# FrequencyCounter.net
KiCad netlist of a schematic drawn in EAGLE
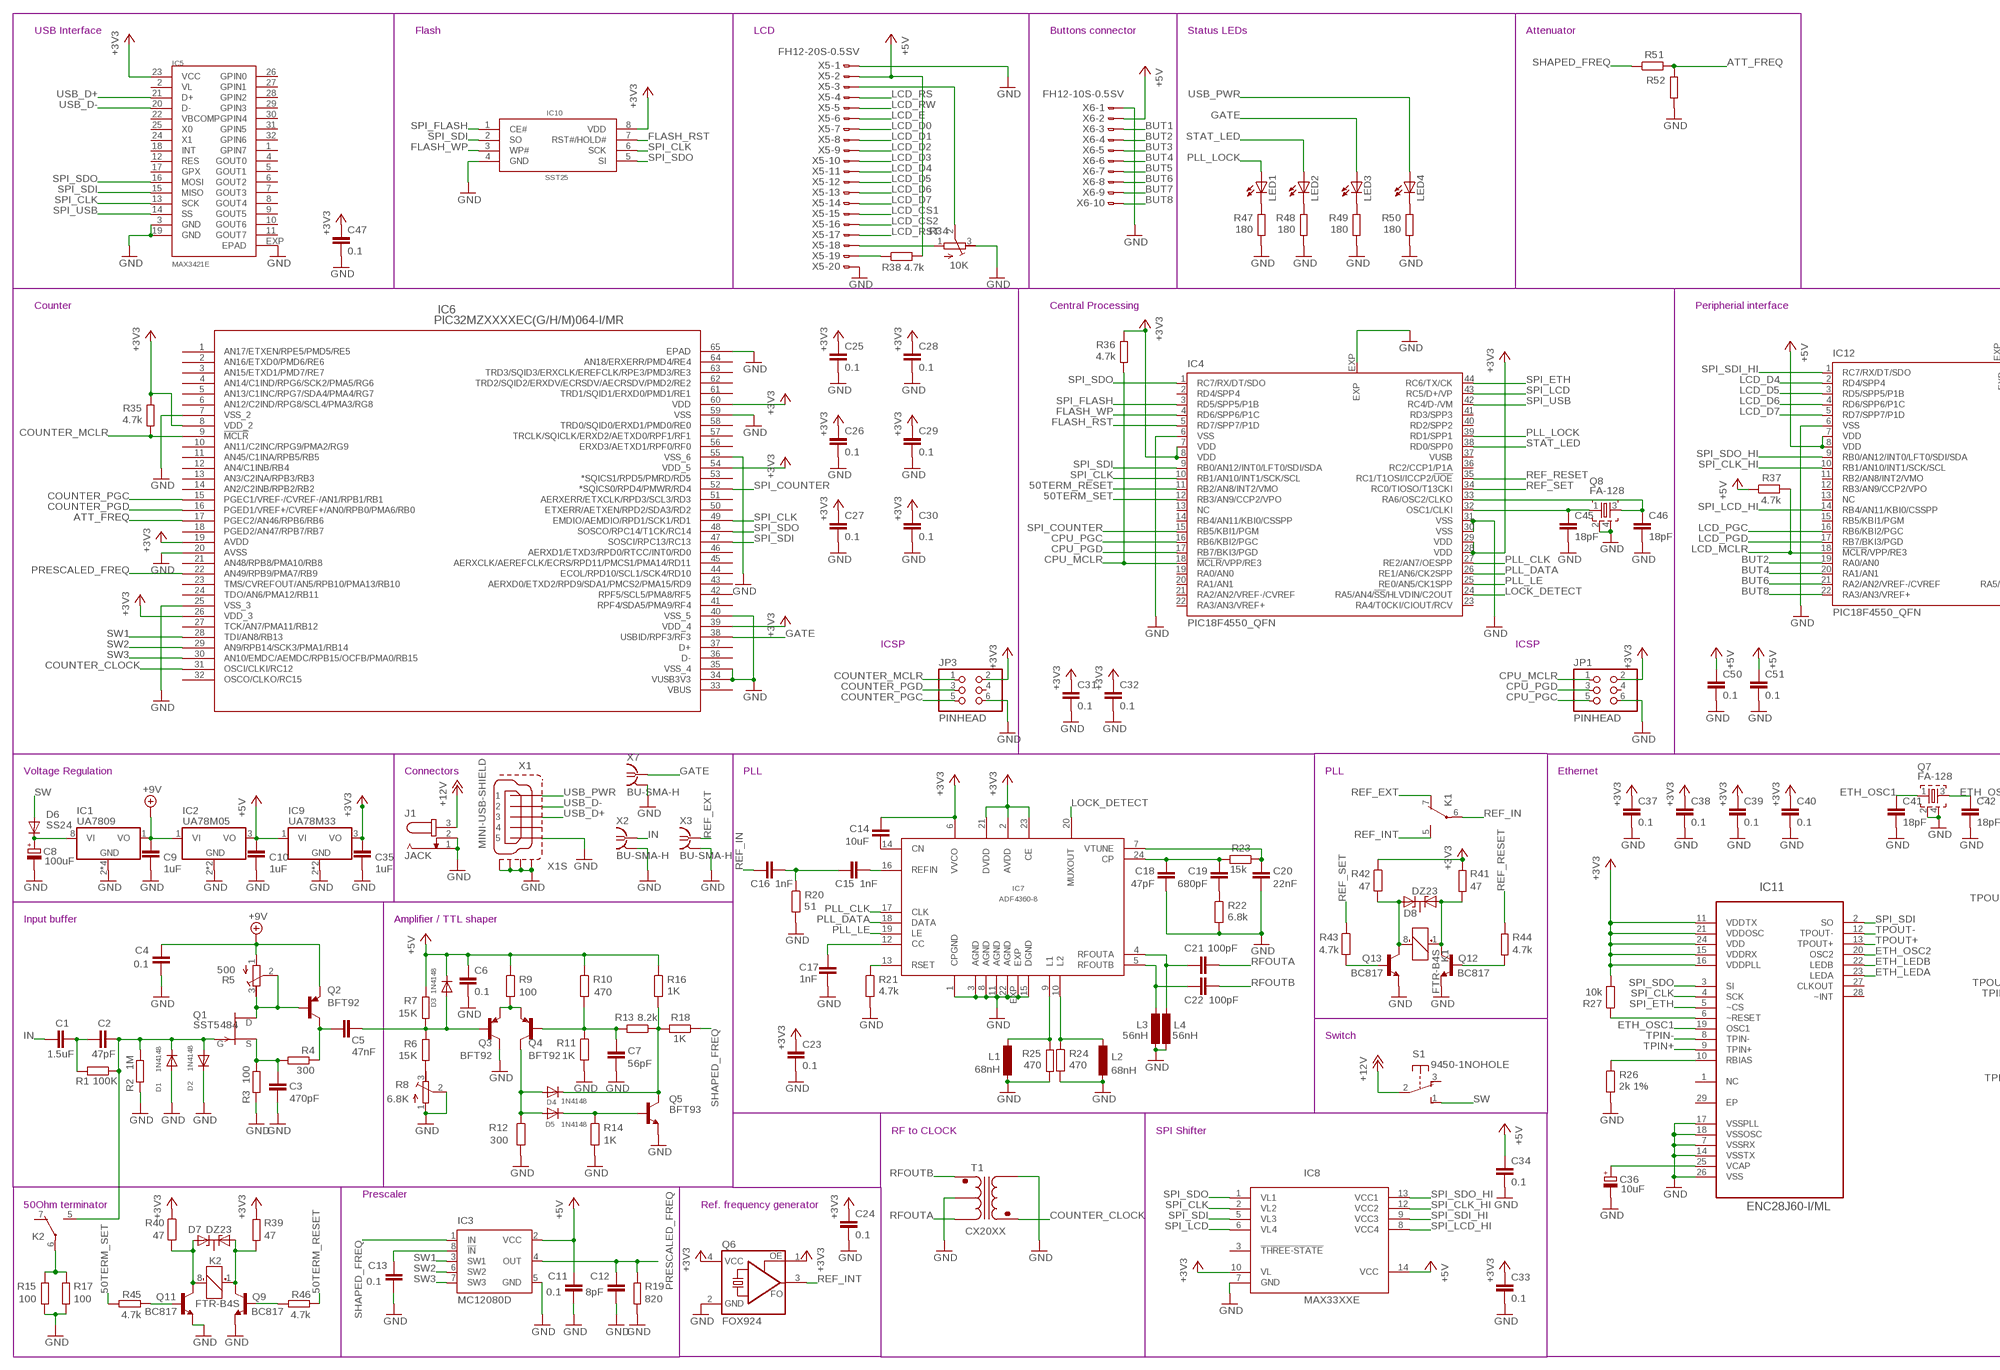
[diagram p0: schematic, sheet 1, part 1 of 2]
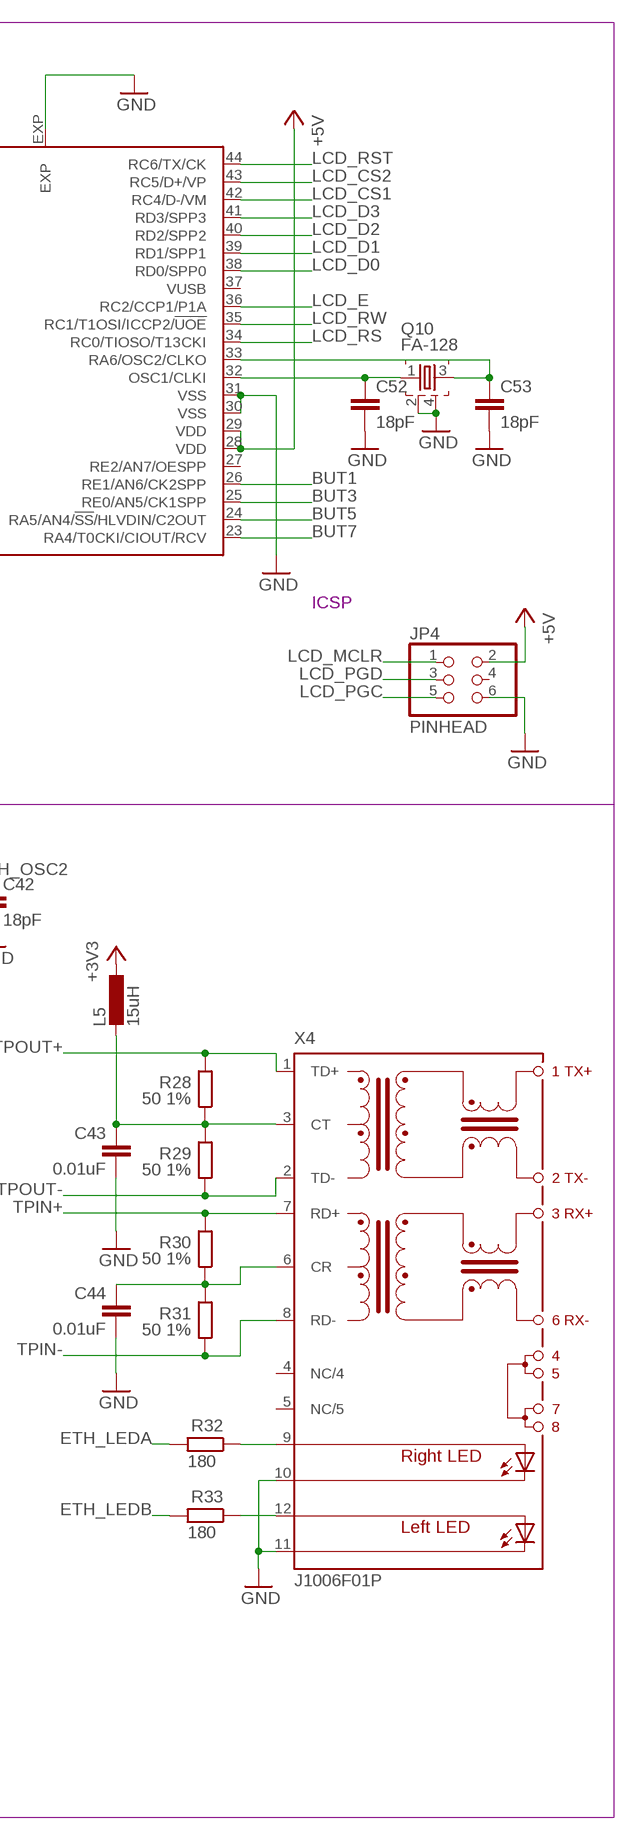
[diagram p1: schematic, sheet 1, part 2 of 2]

(export (version "E")
  (design (tool "Eeschema 10.0.6"))
  (components
    (comp (ref "C1")
      (value "1.5uF")
      (footprint "eagle-import:C0603")
      (libsource (lib "eagle-import") (part "C-EUC0603"))
    )
    (comp (ref "C2")
      (value "47pF")
      (footprint "eagle-import:C0603")
      (libsource (lib "eagle-import") (part "C-EUC0603"))
    )
    (comp (ref "C3")
      (value "470pF")
      (footprint "eagle-import:C0603")
      (libsource (lib "eagle-import") (part "C-EUC0603"))
    )
    (comp (ref "C4")
      (value "0.1")
      (footprint "eagle-import:C0603")
      (libsource (lib "eagle-import") (part "C-EUC0603"))
    )
    (comp (ref "C5")
      (value "47nF")
      (footprint "eagle-import:C0603")
      (libsource (lib "eagle-import") (part "C-EUC0603"))
    )
    (comp (ref "C6")
      (value "0.1")
      (footprint "eagle-import:C0603")
      (libsource (lib "eagle-import") (part "C-EUC0603"))
    )
    (comp (ref "C7")
      (value "56pF")
      (footprint "eagle-import:C0603")
      (libsource (lib "eagle-import") (part "C-EUC0603"))
    )
    (comp (ref "C8")
      (value "100uF")
      (footprint "eagle-import:D_7343-31R")
      (libsource (lib "eagle-import") (part "CPOL-EUD/7343-31R"))
    )
    (comp (ref "C9")
      (value "1uF")
      (footprint "eagle-import:C0603")
      (libsource (lib "eagle-import") (part "C-EUC0603"))
    )
    (comp (ref "C10")
      (value "1uF")
      (footprint "eagle-import:C0603")
      (libsource (lib "eagle-import") (part "C-EUC0603"))
    )
    (comp (ref "C11")
      (value "0.1")
      (footprint "eagle-import:C0603")
      (libsource (lib "eagle-import") (part "C-EUC0603"))
    )
    (comp (ref "C12")
      (value "8pF")
      (footprint "eagle-import:C0603")
      (libsource (lib "eagle-import") (part "C-EUC0603"))
    )
    (comp (ref "C13")
      (value "0.1")
      (footprint "eagle-import:C0603")
      (libsource (lib "eagle-import") (part "C-EUC0603"))
    )
    (comp (ref "C14")
      (value "10uF")
      (footprint "eagle-import:C0603")
      (libsource (lib "eagle-import") (part "C-EUC0603"))
    )
    (comp (ref "C15")
      (value "1nF")
      (footprint "eagle-import:C0603")
      (libsource (lib "eagle-import") (part "C-EUC0603"))
    )
    (comp (ref "C16")
      (value "1nF")
      (footprint "eagle-import:C0603")
      (libsource (lib "eagle-import") (part "C-EUC0603"))
    )
    (comp (ref "C17")
      (value "1nF")
      (footprint "eagle-import:C0603")
      (libsource (lib "eagle-import") (part "C-EUC0603"))
    )
    (comp (ref "C18")
      (value "47pF")
      (footprint "eagle-import:C0603")
      (libsource (lib "eagle-import") (part "C-EUC0603"))
    )
    (comp (ref "C19")
      (value "680pF")
      (footprint "eagle-import:C0603")
      (libsource (lib "eagle-import") (part "C-EUC0603"))
    )
    (comp (ref "C20")
      (value "22nF")
      (footprint "eagle-import:C0603")
      (libsource (lib "eagle-import") (part "C-EUC0603"))
    )
    (comp (ref "C21")
      (value "100pF")
      (footprint "eagle-import:C0603")
      (libsource (lib "eagle-import") (part "C-EUC0603"))
    )
    (comp (ref "C22")
      (value "100pF")
      (footprint "eagle-import:C0603")
      (libsource (lib "eagle-import") (part "C-EUC0603"))
    )
    (comp (ref "C23")
      (value "0.1")
      (footprint "eagle-import:C0603")
      (libsource (lib "eagle-import") (part "C-EUC0603"))
    )
    (comp (ref "C24")
      (value "0.1")
      (footprint "eagle-import:C0603")
      (libsource (lib "eagle-import") (part "C-EUC0603"))
    )
    (comp (ref "C25")
      (value "0.1")
      (footprint "eagle-import:C0603")
      (libsource (lib "eagle-import") (part "C-EUC0603"))
    )
    (comp (ref "C26")
      (value "0.1")
      (footprint "eagle-import:C0603")
      (libsource (lib "eagle-import") (part "C-EUC0603"))
    )
    (comp (ref "C27")
      (value "0.1")
      (footprint "eagle-import:C0603")
      (libsource (lib "eagle-import") (part "C-EUC0603"))
    )
    (comp (ref "C28")
      (value "0.1")
      (footprint "eagle-import:C0603")
      (libsource (lib "eagle-import") (part "C-EUC0603"))
    )
    (comp (ref "C29")
      (value "0.1")
      (footprint "eagle-import:C0603")
      (libsource (lib "eagle-import") (part "C-EUC0603"))
    )
    (comp (ref "C30")
      (value "0.1")
      (footprint "eagle-import:C0603")
      (libsource (lib "eagle-import") (part "C-EUC0603"))
    )
    (comp (ref "C31")
      (value "0.1")
      (footprint "eagle-import:C0603")
      (libsource (lib "eagle-import") (part "C-EUC0603"))
    )
    (comp (ref "C32")
      (value "0.1")
      (footprint "eagle-import:C0603")
      (libsource (lib "eagle-import") (part "C-EUC0603"))
    )
    (comp (ref "C33")
      (value "0.1")
      (footprint "eagle-import:C0603")
      (libsource (lib "eagle-import") (part "C-EUC0603"))
    )
    (comp (ref "C34")
      (value "0.1")
      (footprint "eagle-import:C0603")
      (libsource (lib "eagle-import") (part "C-EUC0603"))
    )
    (comp (ref "C35")
      (value "1uF")
      (footprint "eagle-import:C0603")
      (libsource (lib "eagle-import") (part "C-EUC0603"))
    )
    (comp (ref "C36")
      (value "10uF")
      (footprint "eagle-import:B_3528-21R")
      (libsource (lib "eagle-import") (part "CPOL-EUB/3528-21R"))
    )
    (comp (ref "C37")
      (value "0.1")
      (footprint "eagle-import:C0603")
      (libsource (lib "eagle-import") (part "C-EUC0603"))
    )
    (comp (ref "C38")
      (value "0.1")
      (footprint "eagle-import:C0603")
      (libsource (lib "eagle-import") (part "C-EUC0603"))
    )
    (comp (ref "C39")
      (value "0.1")
      (footprint "eagle-import:C0603")
      (libsource (lib "eagle-import") (part "C-EUC0603"))
    )
    (comp (ref "C40")
      (value "0.1")
      (footprint "eagle-import:C0603")
      (libsource (lib "eagle-import") (part "C-EUC0603"))
    )
    (comp (ref "C41")
      (value "18pF")
      (footprint "eagle-import:C0603")
      (libsource (lib "eagle-import") (part "C-EUC0603"))
    )
    (comp (ref "C42")
      (value "18pF")
      (footprint "eagle-import:C0603")
      (libsource (lib "eagle-import") (part "C-EUC0603"))
    )
    (comp (ref "C43")
      (value "0.01uF")
      (footprint "eagle-import:C0603")
      (libsource (lib "eagle-import") (part "C-EUC0603"))
    )
    (comp (ref "C44")
      (value "0.01uF")
      (footprint "eagle-import:C0603")
      (libsource (lib "eagle-import") (part "C-EUC0603"))
    )
    (comp (ref "C45")
      (value "18pF")
      (footprint "eagle-import:C0603")
      (libsource (lib "eagle-import") (part "C-EUC0603"))
    )
    (comp (ref "C46")
      (value "18pF")
      (footprint "eagle-import:C0603")
      (libsource (lib "eagle-import") (part "C-EUC0603"))
    )
    (comp (ref "C47")
      (value "0.1")
      (footprint "eagle-import:C0603")
      (libsource (lib "eagle-import") (part "C-EUC0603"))
    )
    (comp (ref "C50")
      (value "0.1")
      (footprint "eagle-import:C0603")
      (libsource (lib "eagle-import") (part "C-EUC0603"))
    )
    (comp (ref "C51")
      (value "0.1")
      (footprint "eagle-import:C0603")
      (libsource (lib "eagle-import") (part "C-EUC0603"))
    )
    (comp (ref "C52")
      (value "18pF")
      (footprint "eagle-import:C0603")
      (libsource (lib "eagle-import") (part "C-EUC0603"))
    )
    (comp (ref "C53")
      (value "18pF")
      (footprint "eagle-import:C0603")
      (libsource (lib "eagle-import") (part "C-EUC0603"))
    )
    (comp (ref "D1")
      (value "1N4148")
      (footprint "eagle-import:SOD-123")
      (libsource (lib "eagle-import") (part "DIODESOD-123"))
    )
    (comp (ref "D2")
      (value "1N4148")
      (footprint "eagle-import:SOD-123")
      (libsource (lib "eagle-import") (part "DIODESOD-123"))
    )
    (comp (ref "D3")
      (value "1N4148")
      (footprint "eagle-import:SOD-123")
      (libsource (lib "eagle-import") (part "DIODESOD-123"))
    )
    (comp (ref "D4")
      (value "1N4148")
      (footprint "eagle-import:SOD-123")
      (libsource (lib "eagle-import") (part "DIODESOD-123"))
    )
    (comp (ref "D5")
      (value "1N4148")
      (footprint "eagle-import:SOD-123")
      (libsource (lib "eagle-import") (part "DIODESOD-123"))
    )
    (comp (ref "D6")
      (value "SS24")
      (footprint "eagle-import:DO214AA")
      (libsource (lib "eagle-import") (part "DIODE-DO214AA"))
    )
    (comp (ref "D7")
      (value "DZ23")
      (footprint "eagle-import:SOT23")
      (libsource (lib "eagle-import") (part "DZ23"))
    )
    (comp (ref "D8")
      (value "DZ23")
      (footprint "eagle-import:SOT23")
      (libsource (lib "eagle-import") (part "DZ23"))
    )
    (comp (ref "IC1")
      (value "UA7809")
      (footprint "eagle-import:SOIC8")
      (libsource (lib "eagle-import") (part "UA78XX"))
    )
    (comp (ref "IC2")
      (value "UA78M05")
      (footprint "eagle-import:SOT223")
      (libsource (lib "eagle-import") (part "UA78MXX"))
    )
    (comp (ref "IC3")
      (value "MC12080D")
      (footprint "eagle-import:SO08")
      (fields (field (name "MF") "ON SEMICONDUCTOR"))
      (libsource (lib "eagle-import") (part "MC12080D"))
    )
    (comp (ref "IC4")
      (value "PIC18F4550_QFN")
      (footprint "eagle-import:QFN44ML8X8")
      (fields (field (name "MF") "MICROCHIP") (field (name "MPN") "PIC18F4550-I/ML"))
      (libsource (lib "eagle-import") (part "PIC18F4_QFN550"))
    )
    (comp (ref "IC5")
      (value "MAX3421E")
      (footprint "eagle-import:TQFN32")
      (libsource (lib "eagle-import") (part "MAX3421ETQFN32"))
    )
    (comp (ref "IC6")
      (value "PIC32MZXXXXEC(G/H/M)064-I/MR")
      (footprint "eagle-import:QFN64_9X9MC")
      (fields (field (name "MANUFACTURER_PART_NUMBER") "pic32mz1024ecg064-i/mr"))
      (libsource (lib "eagle-import") (part "PIC32MZXXXXEC(G/H/M)064-I/MR"))
    )
    (comp (ref "IC7")
      (value "ADF4360-8")
      (footprint "eagle-import:LFCSP24")
      (libsource (lib "eagle-import") (part "ADF4360"))
    )
    (comp (ref "IC8")
      (value "MAX33XXE")
      (footprint "eagle-import:TSSOP14")
      (libsource (lib "eagle-import") (part "MAX33XXE"))
    )
    (comp (ref "IC9")
      (value "UA78M33")
      (footprint "eagle-import:SOT223")
      (libsource (lib "eagle-import") (part "UA78MXX"))
    )
    (comp (ref "IC10")
      (value "SST25")
      (footprint "eagle-import:SOIC8")
      (libsource (lib "eagle-import") (part "SST25"))
    )
    (comp (ref "IC11")
      (value "ENC28J60-I/ML")
      (footprint "eagle-import:QFN65P600X600X100-29N")
      (libsource (lib "eagle-import") (part "ENC28J60-I/ML"))
    )
    (comp (ref "IC12")
      (value "PIC18F4550_QFN")
      (footprint "eagle-import:QFN44ML8X8")
      (fields (field (name "MF") "MICROCHIP") (field (name "MPN") "PIC18F4550-I/ML"))
      (libsource (lib "eagle-import") (part "PIC18F4_QFN550"))
    )
    (comp (ref "J1")
      (value "JACK")
      (footprint "eagle-import:SPC4077")
      (libsource (lib "eagle-import") (part "JACK-PLUG0"))
    )
    (comp (ref "JP1")
      (value "PINHEAD")
      (footprint "eagle-import:2X03_1.27")
      (libsource (lib "eagle-import") (part "PINHD-2X32X03/1.27MM"))
    )
    (comp (ref "JP3")
      (value "PINHEAD")
      (footprint "eagle-import:2X03_1.27")
      (libsource (lib "eagle-import") (part "PINHD-2X32X03/1.27MM"))
    )
    (comp (ref "JP4")
      (value "PINHEAD")
      (footprint "eagle-import:2X03_1.27")
      (libsource (lib "eagle-import") (part "PINHD-2X32X03/1.27MM"))
    )
    (comp (ref "K1")
      (value "FTR-B4S")
      (footprint "eagle-import:FTR-B4S")
      (libsource (lib "eagle-import") (part "FTR-B4S"))
    )
    (comp (ref "K2")
      (value "FTR-B4S")
      (footprint "eagle-import:FTR-B4S")
      (libsource (lib "eagle-import") (part "FTR-B4S"))
    )
    (comp (ref "L1")
      (value "68nH")
      (footprint "eagle-import:L2012C")
      (libsource (lib "eagle-import") (part "L-EUL2012C"))
    )
    (comp (ref "L2")
      (value "68nH")
      (footprint "eagle-import:L2012C")
      (libsource (lib "eagle-import") (part "L-EUL2012C"))
    )
    (comp (ref "L3")
      (value "56nH")
      (footprint "eagle-import:L2012C")
      (libsource (lib "eagle-import") (part "L-EUL2012C"))
    )
    (comp (ref "L4")
      (value "56nH")
      (footprint "eagle-import:L2012C")
      (libsource (lib "eagle-import") (part "L-EUL2012C"))
    )
    (comp (ref "L5")
      (value "15uH")
      (footprint "eagle-import:L2012C")
      (libsource (lib "eagle-import") (part "resistor_L-EUL2012C"))
    )
    (comp (ref "LED1")
      (value "LEDCHIP-LED0805")
      (footprint "eagle-import:CHIP-LED0805")
      (libsource (lib "eagle-import") (part "LEDCHIP-LED0805"))
    )
    (comp (ref "LED2")
      (value "LEDCHIP-LED0805")
      (footprint "eagle-import:CHIP-LED0805")
      (libsource (lib "eagle-import") (part "LEDCHIP-LED0805"))
    )
    (comp (ref "LED3")
      (value "LEDCHIP-LED0805")
      (footprint "eagle-import:CHIP-LED0805")
      (libsource (lib "eagle-import") (part "LEDCHIP-LED0805"))
    )
    (comp (ref "LED4")
      (value "LEDCHIP-LED0805")
      (footprint "eagle-import:CHIP-LED0805")
      (libsource (lib "eagle-import") (part "LEDCHIP-LED0805"))
    )
    (comp (ref "Q1")
      (value "SST5484")
      (footprint "eagle-import:SOT23")
      (libsource (lib "eagle-import") (part "?548SST4"))
    )
    (comp (ref "Q2")
      (value "BFT92")
      (footprint "eagle-import:SOT23-BEC")
      (libsource (lib "eagle-import") (part "-PNP-SOT23-BECBC807-16"))
    )
    (comp (ref "Q3")
      (value "BFT92")
      (footprint "eagle-import:SOT23-BEC")
      (libsource (lib "eagle-import") (part "-PNP-SOT23-BECBC807-16"))
    )
    (comp (ref "Q4")
      (value "BFT92")
      (footprint "eagle-import:SOT23-BEC")
      (libsource (lib "eagle-import") (part "-PNP-SOT23-BECBC807-16"))
    )
    (comp (ref "Q5")
      (value "BFT93")
      (footprint "eagle-import:SOT23-BEC")
      (libsource (lib "eagle-import") (part "-NPN-SOT23-BECBC808"))
    )
    (comp (ref "Q6")
      (value "FOX924")
      (footprint "eagle-import:FOX924")
      (libsource (lib "eagle-import") (part "FOX924"))
    )
    (comp (ref "Q7")
      (value "FA-128")
      (footprint "eagle-import:FA-128")
      (libsource (lib "eagle-import") (part "FA-128"))
    )
    (comp (ref "Q8")
      (value "FA-128")
      (footprint "eagle-import:FA-128")
      (libsource (lib "eagle-import") (part "FA-128"))
    )
    (comp (ref "Q9")
      (value "BC817")
      (footprint "eagle-import:SOT23-BEC")
      (libsource (lib "eagle-import") (part "-NPN-SOT23-BECBC817-16"))
    )
    (comp (ref "Q10")
      (value "FA-128")
      (footprint "eagle-import:FA-128")
      (libsource (lib "eagle-import") (part "FA-128"))
    )
    (comp (ref "Q11")
      (value "BC817")
      (footprint "eagle-import:SOT23-BEC")
      (libsource (lib "eagle-import") (part "-NPN-SOT23-BECBC817-16"))
    )
    (comp (ref "Q12")
      (value "BC817")
      (footprint "eagle-import:SOT23-BEC")
      (libsource (lib "eagle-import") (part "-NPN-SOT23-BECBC817-16"))
    )
    (comp (ref "Q13")
      (value "BC817")
      (footprint "eagle-import:SOT23-BEC")
      (libsource (lib "eagle-import") (part "-NPN-SOT23-BECBC817-16"))
    )
    (comp (ref "R1")
      (value "100K")
      (footprint "eagle-import:R0603")
      (libsource (lib "eagle-import") (part "R-EU_R0603"))
    )
    (comp (ref "R2")
      (value "1M")
      (footprint "eagle-import:R0603")
      (libsource (lib "eagle-import") (part "R-EU_R0603"))
    )
    (comp (ref "R3")
      (value "100")
      (footprint "eagle-import:R0603")
      (libsource (lib "eagle-import") (part "R-EU_R0603"))
    )
    (comp (ref "R4")
      (value "300")
      (footprint "eagle-import:R0603")
      (libsource (lib "eagle-import") (part "R-EU_R0603"))
    )
    (comp (ref "R5")
      (value "500")
      (footprint "eagle-import:RTRIM4G_J")
      (libsource (lib "eagle-import") (part "R-TRIMM4G/J"))
    )
    (comp (ref "R6")
      (value "15K")
      (footprint "eagle-import:R0603")
      (libsource (lib "eagle-import") (part "R-EU_R0603"))
    )
    (comp (ref "R7")
      (value "15K")
      (footprint "eagle-import:R0603")
      (libsource (lib "eagle-import") (part "R-EU_R0603"))
    )
    (comp (ref "R8")
      (value "6.8K")
      (footprint "eagle-import:RTRIM4G_J")
      (libsource (lib "eagle-import") (part "R-TRIMM4G/J"))
    )
    (comp (ref "R9")
      (value "100")
      (footprint "eagle-import:R0603")
      (libsource (lib "eagle-import") (part "R-EU_R0603"))
    )
    (comp (ref "R10")
      (value "470")
      (footprint "eagle-import:R0603")
      (libsource (lib "eagle-import") (part "R-EU_R0603"))
    )
    (comp (ref "R11")
      (value "1K")
      (footprint "eagle-import:R0603")
      (libsource (lib "eagle-import") (part "R-EU_R0603"))
    )
    (comp (ref "R12")
      (value "300")
      (footprint "eagle-import:R0603")
      (libsource (lib "eagle-import") (part "R-EU_R0603"))
    )
    (comp (ref "R13")
      (value "8.2k")
      (footprint "eagle-import:R0603")
      (libsource (lib "eagle-import") (part "R-EU_R0603"))
    )
    (comp (ref "R14")
      (value "1K")
      (footprint "eagle-import:R0603")
      (libsource (lib "eagle-import") (part "R-EU_R0603"))
    )
    (comp (ref "R15")
      (value "100")
      (footprint "eagle-import:R0603")
      (libsource (lib "eagle-import") (part "R-EU_R0603"))
    )
    (comp (ref "R16")
      (value "1K")
      (footprint "eagle-import:R0603")
      (libsource (lib "eagle-import") (part "R-EU_R0603"))
    )
    (comp (ref "R17")
      (value "100")
      (footprint "eagle-import:R0603")
      (libsource (lib "eagle-import") (part "R-EU_R0603"))
    )
    (comp (ref "R18")
      (value "1K")
      (footprint "eagle-import:R0603")
      (libsource (lib "eagle-import") (part "R-EU_R0603"))
    )
    (comp (ref "R19")
      (value "820")
      (footprint "eagle-import:R0603")
      (libsource (lib "eagle-import") (part "R-EU_R0603"))
    )
    (comp (ref "R20")
      (value "51")
      (footprint "eagle-import:R0603")
      (libsource (lib "eagle-import") (part "R-EU_R0603"))
    )
    (comp (ref "R21")
      (value "4.7k")
      (footprint "eagle-import:R0603")
      (libsource (lib "eagle-import") (part "R-EU_R0603"))
    )
    (comp (ref "R22")
      (value "6.8k")
      (footprint "eagle-import:R0603")
      (libsource (lib "eagle-import") (part "R-EU_R0603"))
    )
    (comp (ref "R23")
      (value "15k")
      (footprint "eagle-import:R0603")
      (libsource (lib "eagle-import") (part "R-EU_R0603"))
    )
    (comp (ref "R24")
      (value "470")
      (footprint "eagle-import:R0603")
      (libsource (lib "eagle-import") (part "R-EU_R0603"))
    )
    (comp (ref "R25")
      (value "470")
      (footprint "eagle-import:R0603")
      (libsource (lib "eagle-import") (part "R-EU_R0603"))
    )
    (comp (ref "R26")
      (value "2k 1%")
      (footprint "eagle-import:R0603")
      (libsource (lib "eagle-import") (part "R-EU_R0603"))
    )
    (comp (ref "R27")
      (value "10k")
      (footprint "eagle-import:R0603")
      (libsource (lib "eagle-import") (part "R-EU_R0603"))
    )
    (comp (ref "R28")
      (value "50 1%")
      (footprint "eagle-import:R0603")
      (libsource (lib "eagle-import") (part "R-EU_R0603"))
    )
    (comp (ref "R29")
      (value "50 1%")
      (footprint "eagle-import:R0603")
      (libsource (lib "eagle-import") (part "R-EU_R0603"))
    )
    (comp (ref "R30")
      (value "50 1%")
      (footprint "eagle-import:R0603")
      (libsource (lib "eagle-import") (part "R-EU_R0603"))
    )
    (comp (ref "R31")
      (value "50 1%")
      (footprint "eagle-import:R0603")
      (libsource (lib "eagle-import") (part "R-EU_R0603"))
    )
    (comp (ref "R32")
      (value "180")
      (footprint "eagle-import:R0603")
      (libsource (lib "eagle-import") (part "R-EU_R0603"))
    )
    (comp (ref "R33")
      (value "180")
      (footprint "eagle-import:R0603")
      (libsource (lib "eagle-import") (part "R-EU_R0603"))
    )
    (comp (ref "R34")
      (value "10K")
      (footprint "eagle-import:RTRIM4G_J")
      (libsource (lib "eagle-import") (part "R-TRIMM4G/J"))
    )
    (comp (ref "R35")
      (value "4.7k")
      (footprint "eagle-import:R0603")
      (libsource (lib "eagle-import") (part "R-EU_R0603"))
    )
    (comp (ref "R36")
      (value "4.7k")
      (footprint "eagle-import:R0603")
      (libsource (lib "eagle-import") (part "R-EU_R0603"))
    )
    (comp (ref "R37")
      (value "4.7k")
      (footprint "eagle-import:R0603")
      (libsource (lib "eagle-import") (part "R-EU_R0603"))
    )
    (comp (ref "R38")
      (value "4.7k")
      (footprint "eagle-import:R0603")
      (libsource (lib "eagle-import") (part "R-EU_R0603"))
    )
    (comp (ref "R39")
      (value "47")
      (footprint "eagle-import:R0603")
      (libsource (lib "eagle-import") (part "R-EU_R0603"))
    )
    (comp (ref "R40")
      (value "47")
      (footprint "eagle-import:R0603")
      (libsource (lib "eagle-import") (part "R-EU_R0603"))
    )
    (comp (ref "R41")
      (value "47")
      (footprint "eagle-import:R0603")
      (libsource (lib "eagle-import") (part "R-EU_R0603"))
    )
    (comp (ref "R42")
      (value "47")
      (footprint "eagle-import:R0603")
      (libsource (lib "eagle-import") (part "R-EU_R0603"))
    )
    (comp (ref "R43")
      (value "4.7k")
      (footprint "eagle-import:R0603")
      (libsource (lib "eagle-import") (part "R-EU_R0603"))
    )
    (comp (ref "R44")
      (value "4.7k")
      (footprint "eagle-import:R0603")
      (libsource (lib "eagle-import") (part "R-EU_R0603"))
    )
    (comp (ref "R45")
      (value "4.7k")
      (footprint "eagle-import:R0603")
      (libsource (lib "eagle-import") (part "R-EU_R0603"))
    )
    (comp (ref "R46")
      (value "4.7k")
      (footprint "eagle-import:R0603")
      (libsource (lib "eagle-import") (part "R-EU_R0603"))
    )
    (comp (ref "R47")
      (value "180")
      (footprint "eagle-import:R0603")
      (libsource (lib "eagle-import") (part "R-EU_R0603"))
    )
    (comp (ref "R48")
      (value "180")
      (footprint "eagle-import:R0603")
      (libsource (lib "eagle-import") (part "R-EU_R0603"))
    )
    (comp (ref "R49")
      (value "180")
      (footprint "eagle-import:R0603")
      (libsource (lib "eagle-import") (part "R-EU_R0603"))
    )
    (comp (ref "R50")
      (value "180")
      (footprint "eagle-import:R0603")
      (libsource (lib "eagle-import") (part "R-EU_R0603"))
    )
    (comp (ref "R51")
      (value "R-EU_R0603")
      (footprint "eagle-import:R0603")
      (libsource (lib "eagle-import") (part "R-EU_R0603"))
    )
    (comp (ref "R52")
      (value "R-EU_R0603")
      (footprint "eagle-import:R0603")
      (libsource (lib "eagle-import") (part "R-EU_R0603"))
    )
    (comp (ref "S1")
      (value "9450-1NOHOLE")
      (footprint "eagle-import:9450-1-NOHOLE")
      (libsource (lib "eagle-import") (part "9450-1NOHOLE"))
    )
    (comp (ref "T1")
      (value "CX20XX")
      (footprint "eagle-import:PULSE_CX20")
      (libsource (lib "eagle-import") (part "CX20XX"))
    )
    (comp (ref "X1")
      (value "MINI-USB-SHIELD")
      (footprint "eagle-import:UX60A-MB-5ST")
      (libsource (lib "eagle-import") (part "MINI-USB-SHIELD-UX60A-MB-5ST"))
    )
    (comp (ref "X2")
      (value "BU-SMA-H")
      (footprint "eagle-import:BU-SMA-H")
      (libsource (lib "eagle-import") (part "BU-SMA-H"))
    )
    (comp (ref "X3")
      (value "BU-SMA-H")
      (footprint "eagle-import:BU-SMA-H")
      (libsource (lib "eagle-import") (part "BU-SMA-H"))
    )
    (comp (ref "X4")
      (value "J1006F01P")
      (footprint "eagle-import:J1")
      (libsource (lib "eagle-import") (part "J1006F01P"))
    )
    (comp (ref "X5")
      (value "FH12-20S-0.5SV")
      (footprint "eagle-import:FH12-20S-0.5SV")
      (libsource (lib "eagle-import") (part "FH12-20S-0.5SV"))
    )
    (comp (ref "X6")
      (value "FH12-10S-0.5SV")
      (footprint "eagle-import:FH12-10S-0.5SV")
      (libsource (lib "eagle-import") (part "FH12-10S-0.5SV"))
    )
    (comp (ref "X7")
      (value "BU-SMA-H")
      (footprint "eagle-import:BU-SMA-H")
      (libsource (lib "eagle-import") (part "BU-SMA-H"))
    )
  )
  (nets
    (net (code "1") (name "+3V3") (class "Default")
      (node (ref "C14") (pin "2") (pinfunction "2_2") (pintype "passive"))
      (node (ref "C23") (pin "1") (pinfunction "1_1") (pintype "passive"))
      (node (ref "C24") (pin "1") (pinfunction "1_1") (pintype "passive"))
      (node (ref "C25") (pin "1") (pinfunction "1_1") (pintype "passive"))
      (node (ref "C26") (pin "1") (pinfunction "1_1") (pintype "passive"))
      (node (ref "C27") (pin "1") (pinfunction "1_1") (pintype "passive"))
      (node (ref "C28") (pin "1") (pinfunction "1_1") (pintype "passive"))
      (node (ref "C29") (pin "1") (pinfunction "1_1") (pintype "passive"))
      (node (ref "C30") (pin "1") (pinfunction "1_1") (pintype "passive"))
      (node (ref "C31") (pin "1") (pinfunction "1_1") (pintype "passive"))
      (node (ref "C32") (pin "1") (pinfunction "1_1") (pintype "passive"))
      (node (ref "C33") (pin "1") (pinfunction "1_1") (pintype "passive"))
      (node (ref "C35") (pin "1") (pinfunction "1_1") (pintype "passive"))
      (node (ref "C37") (pin "1") (pinfunction "1_1") (pintype "passive"))
      (node (ref "C38") (pin "1") (pinfunction "1_1") (pintype "passive"))
      (node (ref "C39") (pin "1") (pinfunction "1_1") (pintype "passive"))
      (node (ref "C40") (pin "1") (pinfunction "1_1") (pintype "passive"))
      (node (ref "C47") (pin "1") (pinfunction "1_1") (pintype "passive"))
      (node (ref "IC10") (pin "8") (pinfunction "VDD_8") (pintype "power_in"))
      (node (ref "IC11") (pin "11") (pinfunction "VDDTX_11") (pintype "power_in"))
      (node (ref "IC11") (pin "15") (pinfunction "VDDRX_15") (pintype "power_in"))
      (node (ref "IC11") (pin "16") (pinfunction "VDDPLL_16") (pintype "power_in"))
      (node (ref "IC11") (pin "21") (pinfunction "VDDOSC_21") (pintype "power_in"))
      (node (ref "IC11") (pin "24") (pinfunction "VDD_24") (pintype "power_in"))
      (node (ref "IC4") (pin "28") (pinfunction "VDD_28") (pintype "power_in"))
      (node (ref "IC4") (pin "29") (pinfunction "VDD_29") (pintype "power_in"))
      (node (ref "IC4") (pin "7") (pinfunction "VDD_7") (pintype "power_in"))
      (node (ref "IC4") (pin "8") (pinfunction "VDD_8") (pintype "power_in"))
      (node (ref "IC5") (pin "23") (pinfunction "VCC_23") (pintype "bidirectional"))
      (node (ref "IC6") (pin "19") (pinfunction "AVDD_19") (pintype "power_in"))
      (node (ref "IC6") (pin "26") (pinfunction "VDD_3_26") (pintype "power_in"))
      (node (ref "IC6") (pin "39") (pinfunction "VDD_4_39") (pintype "power_in"))
      (node (ref "IC6") (pin "54") (pinfunction "VDD_5_54") (pintype "power_in"))
      (node (ref "IC6") (pin "60") (pinfunction "VDD_60") (pintype "power_in"))
      (node (ref "IC6") (pin "8") (pinfunction "VDD_2_8") (pintype "power_in"))
      (node (ref "IC7") (pin "2") (pinfunction "AVDD_2") (pintype "bidirectional"))
      (node (ref "IC7") (pin "21") (pinfunction "DVDD_21") (pintype "bidirectional"))
      (node (ref "IC7") (pin "23") (pinfunction "CE_23") (pintype "bidirectional"))
      (node (ref "IC7") (pin "6") (pinfunction "VVCO_6") (pintype "bidirectional"))
      (node (ref "IC8") (pin "10") (pinfunction "VL_10") (pintype "power_in"))
      (node (ref "IC9") (pin "3") (pinfunction "VO_3") (pintype "passive"))
      (node (ref "JP1") (pin "2") (pinfunction "2_2") (pintype "passive"))
      (node (ref "JP3") (pin "2") (pinfunction "2_2") (pintype "passive"))
      (node (ref "L5") (pin "1") (pinfunction "1_1") (pintype "passive"))
      (node (ref "Q6") (pin "1") (pinfunction "OE_1") (pintype "input"))
      (node (ref "Q6") (pin "4") (pinfunction "VCC_4") (pintype "power_in"))
      (node (ref "R27") (pin "2") (pinfunction "2_2") (pintype "passive"))
      (node (ref "R35") (pin "1") (pinfunction "1_1") (pintype "passive"))
      (node (ref "R36") (pin "1") (pinfunction "1_1") (pintype "passive"))
      (node (ref "R39") (pin "1") (pinfunction "1_1") (pintype "passive"))
      (node (ref "R40") (pin "1") (pinfunction "1_1") (pintype "passive"))
      (node (ref "R41") (pin "1") (pinfunction "1_1") (pintype "passive"))
      (node (ref "R42") (pin "1") (pinfunction "1_1") (pintype "passive"))
    )
    (net (code "2") (name "+5V") (class "Default")
      (node (ref "C10") (pin "1") (pinfunction "1_1") (pintype "passive"))
      (node (ref "C11") (pin "1") (pinfunction "1_1") (pintype "passive"))
      (node (ref "C34") (pin "1") (pinfunction "1_1") (pintype "passive"))
      (node (ref "C50") (pin "1") (pinfunction "1_1") (pintype "passive"))
      (node (ref "C51") (pin "1") (pinfunction "1_1") (pintype "passive"))
      (node (ref "C6") (pin "1") (pinfunction "1_1") (pintype "passive"))
      (node (ref "D3") (pin "C") (pinfunction "C_C") (pintype "passive"))
      (node (ref "IC12") (pin "28") (pinfunction "VDD_28") (pintype "power_in"))
      (node (ref "IC12") (pin "29") (pinfunction "VDD_29") (pintype "power_in"))
      (node (ref "IC12") (pin "7") (pinfunction "VDD_7") (pintype "power_in"))
      (node (ref "IC12") (pin "8") (pinfunction "VDD_8") (pintype "power_in"))
      (node (ref "IC2") (pin "3") (pinfunction "VO_3") (pintype "passive"))
      (node (ref "IC3") (pin "2") (pinfunction "VCC_2") (pintype "power_in"))
      (node (ref "IC8") (pin "14") (pinfunction "VCC_14") (pintype "power_in"))
      (node (ref "IC9") (pin "1") (pinfunction "VI_1") (pintype "input"))
      (node (ref "JP4") (pin "2") (pinfunction "2_2") (pintype "passive"))
      (node (ref "R10") (pin "1") (pinfunction "1_1") (pintype "passive"))
      (node (ref "R16") (pin "1") (pinfunction "1_1") (pintype "passive"))
      (node (ref "R37") (pin "1") (pinfunction "1_1") (pintype "passive"))
      (node (ref "R38") (pin "2") (pinfunction "2_2") (pintype "passive"))
      (node (ref "R7") (pin "1") (pinfunction "1_1") (pintype "passive"))
      (node (ref "R9") (pin "1") (pinfunction "1_1") (pintype "passive"))
      (node (ref "X5") (pin "2") (pinfunction "1_2") (pintype "passive"))
      (node (ref "X6") (pin "2") (pinfunction "1_2") (pintype "passive"))
    )
    (net (code "3") (name "+9V") (class "Default")
      (node (ref "C4") (pin "1") (pinfunction "1_1") (pintype "passive"))
      (node (ref "C9") (pin "1") (pinfunction "1_1") (pintype "passive"))
      (node (ref "IC1") (pin "1") (pinfunction "VO_1") (pintype "passive"))
      (node (ref "IC2") (pin "1") (pinfunction "VI_1") (pintype "input"))
      (node (ref "Q2") (pin "E") (pinfunction "E_E") (pintype "passive"))
      (node (ref "R5") (pin "1") (pinfunction "A_1") (pintype "passive"))
    )
    (net (code "4") (name "+12V") (class "Default")
      (node (ref "J1") (pin "3") (pinfunction "3_3") (pintype "passive"))
      (node (ref "S1") (pin "2") (pinfunction "P_2") (pintype "passive"))
    )
    (net (code "5") (name "/50TERM_RESET") (class "Default")
      (node (ref "IC4") (pin "11") (pinfunction "RB2/AN8/INT2/VMO_11") (pintype "bidirectional"))
      (node (ref "R46") (pin "2") (pinfunction "2_2") (pintype "passive"))
    )
    (net (code "6") (name "/50TERM_SET") (class "Default")
      (node (ref "IC4") (pin "12") (pinfunction "RB3/AN9/CCP2/VPO_12") (pintype "bidirectional"))
      (node (ref "R45") (pin "1") (pinfunction "1_1") (pintype "passive"))
    )
    (net (code "7") (name "/ATT_FREQ") (class "Default")
      (node (ref "IC6") (pin "17") (pinfunction "PGEC2/AN46/RPB6/RB6_17") (pintype "bidirectional"))
      (node (ref "R51") (pin "2") (pinfunction "2_2") (pintype "passive"))
      (node (ref "R52") (pin "1") (pinfunction "1_1") (pintype "passive"))
    )
    (net (code "8") (name "/BUT1") (class "Default")
      (node (ref "IC12") (pin "26") (pinfunction "RE1/AN6/CK2SPP_26") (pintype "bidirectional"))
      (node (ref "X6") (pin "3") (pinfunction "1_3") (pintype "passive"))
    )
    (net (code "9") (name "/BUT2") (class "Default")
      (node (ref "IC12") (pin "19") (pinfunction "RA0/AN0_19") (pintype "bidirectional"))
      (node (ref "X6") (pin "4") (pinfunction "1_4") (pintype "passive"))
    )
    (net (code "10") (name "/BUT3") (class "Default")
      (node (ref "IC12") (pin "25") (pinfunction "RE0/AN5/CK1SPP_25") (pintype "bidirectional"))
      (node (ref "X6") (pin "5") (pinfunction "1_5") (pintype "passive"))
    )
    (net (code "11") (name "/BUT4") (class "Default")
      (node (ref "IC12") (pin "20") (pinfunction "RA1/AN1_20") (pintype "bidirectional"))
      (node (ref "X6") (pin "6") (pinfunction "1_6") (pintype "passive"))
    )
    (net (code "12") (name "/BUT5") (class "Default")
      (node (ref "IC12") (pin "24") (pinfunction "RA5/AN4/~{SS}/HLVDIN/C2OUT_24") (pintype "bidirectional"))
      (node (ref "X6") (pin "7") (pinfunction "1_7") (pintype "passive"))
    )
    (net (code "13") (name "/BUT6") (class "Default")
      (node (ref "IC12") (pin "21") (pinfunction "RA2/AN2/VREF-/CVREF_21") (pintype "bidirectional"))
      (node (ref "X6") (pin "8") (pinfunction "1_8") (pintype "passive"))
    )
    (net (code "14") (name "/BUT7") (class "Default")
      (node (ref "IC12") (pin "23") (pinfunction "RA4/T0CKI/CIOUT/RCV_23") (pintype "bidirectional"))
      (node (ref "X6") (pin "9") (pinfunction "1_9") (pintype "passive"))
    )
    (net (code "15") (name "/BUT8") (class "Default")
      (node (ref "IC12") (pin "22") (pinfunction "RA3/AN3/VREF+_22") (pintype "bidirectional"))
      (node (ref "X6") (pin "10") (pinfunction "1_10") (pintype "passive"))
    )
    (net (code "16") (name "/COUNTER_CLOCK") (class "Default")
      (node (ref "IC6") (pin "31") (pinfunction "OSCI/CLKI/RC12_31") (pintype "bidirectional"))
      (node (ref "T1") (pin "P$4") (pinfunction "P$4_P$4") (pintype "passive"))
    )
    (net (code "17") (name "/COUNTER_MCLR") (class "Default")
      (node (ref "IC6") (pin "9") (pinfunction "~{MCLR}_9") (pintype "passive"))
      (node (ref "JP3") (pin "1") (pinfunction "1_1") (pintype "passive"))
      (node (ref "R35") (pin "2") (pinfunction "2_2") (pintype "passive"))
    )
    (net (code "18") (name "/COUNTER_PGC") (class "Default")
      (node (ref "IC6") (pin "15") (pinfunction "PGEC1/VREF-/CVREF-/AN1/RPB1/RB1_15") (pintype "bidirectional"))
      (node (ref "JP3") (pin "5") (pinfunction "5_5") (pintype "passive"))
    )
    (net (code "19") (name "/COUNTER_PGD") (class "Default")
      (node (ref "IC6") (pin "16") (pinfunction "PGED1/VREF+/CVREF+/AN0/RPB0/PMA6/RB0_16") (pintype "bidirectional"))
      (node (ref "JP3") (pin "3") (pinfunction "3_3") (pintype "passive"))
    )
    (net (code "20") (name "/CPU_MCLR") (class "Default")
      (node (ref "IC4") (pin "18") (pinfunction "~{MCLR}/VPP/RE3_18") (pintype "input"))
      (node (ref "JP1") (pin "1") (pinfunction "1_1") (pintype "passive"))
      (node (ref "R36") (pin "2") (pinfunction "2_2") (pintype "passive"))
    )
    (net (code "21") (name "/CPU_PGC") (class "Default")
      (node (ref "IC4") (pin "16") (pinfunction "RB6/KBI2/PGC_16") (pintype "bidirectional"))
      (node (ref "JP1") (pin "5") (pinfunction "5_5") (pintype "passive"))
    )
    (net (code "22") (name "/CPU_PGD") (class "Default")
      (node (ref "IC4") (pin "17") (pinfunction "RB7/BKI3/PGD_17") (pintype "bidirectional"))
      (node (ref "JP1") (pin "3") (pinfunction "3_3") (pintype "passive"))
    )
    (net (code "23") (name "/ETH_LEDA") (class "Default")
      (node (ref "IC11") (pin "23") (pinfunction "LEDA_23") (pintype "output"))
      (node (ref "R32") (pin "2") (pinfunction "2_2") (pintype "passive"))
    )
    (net (code "24") (name "/ETH_LEDB") (class "Default")
      (node (ref "IC11") (pin "22") (pinfunction "LEDB_22") (pintype "output"))
      (node (ref "R33") (pin "2") (pinfunction "2_2") (pintype "passive"))
    )
    (net (code "25") (name "/ETH_OSC1") (class "Default")
      (node (ref "C41") (pin "1") (pinfunction "1_1") (pintype "passive"))
      (node (ref "IC11") (pin "19") (pinfunction "OSC1_19") (pintype "input"))
      (node (ref "Q7") (pin "1") (pinfunction "1_1") (pintype "passive"))
    )
    (net (code "26") (name "/ETH_OSC2") (class "Default")
      (node (ref "C42") (pin "1") (pinfunction "1_1") (pintype "passive"))
      (node (ref "IC11") (pin "20") (pinfunction "OSC2_20") (pintype "output"))
      (node (ref "Q7") (pin "3") (pinfunction "3_3") (pintype "passive"))
    )
    (net (code "27") (name "/FLASH_RST") (class "Default")
      (node (ref "IC10") (pin "7") (pinfunction "RST#/HOLD#_7") (pintype "bidirectional"))
      (node (ref "IC4") (pin "5") (pinfunction "RD7/SPP7/P1D_5") (pintype "bidirectional"))
    )
    (net (code "28") (name "/FLASH_WP") (class "Default")
      (node (ref "IC10") (pin "3") (pinfunction "WP#_3") (pintype "bidirectional"))
      (node (ref "IC4") (pin "4") (pinfunction "RD6/SPP6/P1C_4") (pintype "bidirectional"))
    )
    (net (code "29") (name "/GATE") (class "Default")
      (node (ref "IC6") (pin "38") (pinfunction "USBID/RPF3/RF3_38") (pintype "bidirectional"))
      (node (ref "LED3") (pin "A") (pinfunction "A_A") (pintype "passive"))
      (node (ref "X7") (pin "1") (pinfunction "1_1") (pintype "passive"))
    )
    (net (code "30") (name "/IN") (class "Default")
      (node (ref "C1") (pin "1") (pinfunction "1_1") (pintype "passive"))
      (node (ref "X2") (pin "1") (pinfunction "1_1") (pintype "passive"))
    )
    (net (code "31") (name "/LCD_CS1") (class "Default")
      (node (ref "IC12") (pin "42") (pinfunction "RC4/D-/VM_42") (pintype "bidirectional"))
      (node (ref "X5") (pin "15") (pinfunction "1_15") (pintype "passive"))
    )
    (net (code "32") (name "/LCD_CS2") (class "Default")
      (node (ref "IC12") (pin "43") (pinfunction "RC5/D+/VP_43") (pintype "bidirectional"))
      (node (ref "X5") (pin "16") (pinfunction "1_16") (pintype "passive"))
    )
    (net (code "33") (name "/LCD_D0") (class "Default")
      (node (ref "IC12") (pin "38") (pinfunction "RD0/SPP0_38") (pintype "bidirectional"))
      (node (ref "X5") (pin "7") (pinfunction "1_7") (pintype "passive"))
    )
    (net (code "34") (name "/LCD_D1") (class "Default")
      (node (ref "IC12") (pin "39") (pinfunction "RD1/SPP1_39") (pintype "bidirectional"))
      (node (ref "X5") (pin "8") (pinfunction "1_8") (pintype "passive"))
    )
    (net (code "35") (name "/LCD_D2") (class "Default")
      (node (ref "IC12") (pin "40") (pinfunction "RD2/SPP2_40") (pintype "bidirectional"))
      (node (ref "X5") (pin "9") (pinfunction "1_9") (pintype "passive"))
    )
    (net (code "36") (name "/LCD_D3") (class "Default")
      (node (ref "IC12") (pin "41") (pinfunction "RD3/SPP3_41") (pintype "bidirectional"))
      (node (ref "X5") (pin "10") (pinfunction "1_10") (pintype "passive"))
    )
    (net (code "37") (name "/LCD_D4") (class "Default")
      (node (ref "IC12") (pin "2") (pinfunction "RD4/SPP4_2") (pintype "bidirectional"))
      (node (ref "X5") (pin "11") (pinfunction "1_11") (pintype "passive"))
    )
    (net (code "38") (name "/LCD_D5") (class "Default")
      (node (ref "IC12") (pin "3") (pinfunction "RD5/SPP5/P1B_3") (pintype "bidirectional"))
      (node (ref "X5") (pin "12") (pinfunction "1_12") (pintype "passive"))
    )
    (net (code "39") (name "/LCD_D6") (class "Default")
      (node (ref "IC12") (pin "4") (pinfunction "RD6/SPP6/P1C_4") (pintype "bidirectional"))
      (node (ref "X5") (pin "13") (pinfunction "1_13") (pintype "passive"))
    )
    (net (code "40") (name "/LCD_D7") (class "Default")
      (node (ref "IC12") (pin "5") (pinfunction "RD7/SPP7/P1D_5") (pintype "bidirectional"))
      (node (ref "X5") (pin "14") (pinfunction "1_14") (pintype "passive"))
    )
    (net (code "41") (name "/LCD_E") (class "Default")
      (node (ref "IC12") (pin "36") (pinfunction "RC2/CCP1/P1A_36") (pintype "bidirectional"))
      (node (ref "X5") (pin "6") (pinfunction "1_6") (pintype "passive"))
    )
    (net (code "42") (name "/LCD_MCLR") (class "Default")
      (node (ref "IC12") (pin "18") (pinfunction "~{MCLR}/VPP/RE3_18") (pintype "input"))
      (node (ref "JP4") (pin "1") (pinfunction "1_1") (pintype "passive"))
      (node (ref "R37") (pin "2") (pinfunction "2_2") (pintype "passive"))
    )
    (net (code "43") (name "/LCD_PGC") (class "Default")
      (node (ref "IC12") (pin "16") (pinfunction "RB6/KBI2/PGC_16") (pintype "bidirectional"))
      (node (ref "JP4") (pin "5") (pinfunction "5_5") (pintype "passive"))
    )
    (net (code "44") (name "/LCD_PGD") (class "Default")
      (node (ref "IC12") (pin "17") (pinfunction "RB7/BKI3/PGD_17") (pintype "bidirectional"))
      (node (ref "JP4") (pin "3") (pinfunction "3_3") (pintype "passive"))
    )
    (net (code "45") (name "/LCD_RS") (class "Default")
      (node (ref "IC12") (pin "34") (pinfunction "RC0/TIOSO/T13CKI_34") (pintype "bidirectional"))
      (node (ref "X5") (pin "4") (pinfunction "1_4") (pintype "passive"))
    )
    (net (code "46") (name "/LCD_RST") (class "Default")
      (node (ref "IC12") (pin "44") (pinfunction "RC6/TX/CK_44") (pintype "bidirectional"))
      (node (ref "X5") (pin "17") (pinfunction "1_17") (pintype "passive"))
    )
    (net (code "47") (name "/LCD_RW") (class "Default")
      (node (ref "IC12") (pin "35") (pinfunction "RC1/T1OSI/ICCP2/~{UOE}_35") (pintype "bidirectional"))
      (node (ref "X5") (pin "5") (pinfunction "1_5") (pintype "passive"))
    )
    (net (code "48") (name "/LOCK_DETECT") (class "Default")
      (node (ref "IC4") (pin "24") (pinfunction "RA5/AN4/~{SS}/HLVDIN/C2OUT_24") (pintype "bidirectional"))
      (node (ref "IC7") (pin "20") (pinfunction "MUXOUT_20") (pintype "bidirectional"))
    )
    (net (code "49") (name "/PLL_CLK") (class "Default")
      (node (ref "IC4") (pin "27") (pinfunction "RE2/AN7/OESPP_27") (pintype "bidirectional"))
      (node (ref "IC7") (pin "17") (pinfunction "CLK_17") (pintype "bidirectional"))
    )
    (net (code "50") (name "/PLL_DATA") (class "Default")
      (node (ref "IC4") (pin "26") (pinfunction "RE1/AN6/CK2SPP_26") (pintype "bidirectional"))
      (node (ref "IC7") (pin "18") (pinfunction "DATA_18") (pintype "bidirectional"))
    )
    (net (code "51") (name "/PLL_LE") (class "Default")
      (node (ref "IC4") (pin "25") (pinfunction "RE0/AN5/CK1SPP_25") (pintype "bidirectional"))
      (node (ref "IC7") (pin "19") (pinfunction "LE_19") (pintype "bidirectional"))
    )
    (net (code "52") (name "/PLL_LOCK") (class "Default")
      (node (ref "IC4") (pin "39") (pinfunction "RD1/SPP1_39") (pintype "bidirectional"))
      (node (ref "LED1") (pin "A") (pinfunction "A_A") (pintype "passive"))
    )
    (net (code "53") (name "/PRESCALED_FREQ") (class "Default")
      (node (ref "C12") (pin "1") (pinfunction "1_1") (pintype "passive"))
      (node (ref "IC3") (pin "4") (pinfunction "OUT_4") (pintype "output"))
      (node (ref "IC6") (pin "22") (pinfunction "AN49/RPB9/PMA7/RB9_22") (pintype "bidirectional"))
      (node (ref "R19") (pin "1") (pinfunction "1_1") (pintype "passive"))
    )
    (net (code "54") (name "/REF_EXT") (class "Default")
      (node (ref "K1") (pin "7") (pinfunction "O_7") (pintype "passive"))
      (node (ref "X3") (pin "1") (pinfunction "1_1") (pintype "passive"))
    )
    (net (code "55") (name "/REF_IN") (class "Default")
      (node (ref "C16") (pin "2") (pinfunction "2_2") (pintype "passive"))
      (node (ref "K1") (pin "6") (pinfunction "P_6") (pintype "passive"))
    )
    (net (code "56") (name "/REF_INT") (class "Default")
      (node (ref "K1") (pin "5") (pinfunction "S_5") (pintype "passive"))
      (node (ref "Q6") (pin "3") (pinfunction "FO_3") (pintype "output"))
    )
    (net (code "57") (name "/REF_RESET") (class "Default")
      (node (ref "IC4") (pin "35") (pinfunction "RC1/T1OSI/ICCP2/~{UOE}_35") (pintype "bidirectional"))
      (node (ref "R44") (pin "1") (pinfunction "1_1") (pintype "passive"))
    )
    (net (code "58") (name "/REF_SET") (class "Default")
      (node (ref "IC4") (pin "34") (pinfunction "RC0/TIOSO/T13CKI_34") (pintype "bidirectional"))
      (node (ref "R43") (pin "1") (pinfunction "1_1") (pintype "passive"))
    )
    (net (code "59") (name "/RFOUTA") (class "Default")
      (node (ref "C21") (pin "2") (pinfunction "2_2") (pintype "passive"))
      (node (ref "T1") (pin "P$3") (pinfunction "P$3_P$3") (pintype "passive"))
    )
    (net (code "60") (name "/RFOUTB") (class "Default")
      (node (ref "C22") (pin "1") (pinfunction "1_1") (pintype "passive"))
      (node (ref "T1") (pin "P$1") (pinfunction "P$1_P$1") (pintype "passive"))
    )
    (net (code "61") (name "/SHAPED_FREQ") (class "Default")
      (node (ref "IC3") (pin "1") (pinfunction "IN_1") (pintype "input"))
      (node (ref "R18") (pin "1") (pinfunction "1_1") (pintype "passive"))
      (node (ref "R51") (pin "1") (pinfunction "1_1") (pintype "passive"))
    )
    (net (code "62") (name "/SPI_CLK") (class "Default")
      (node (ref "IC10") (pin "6") (pinfunction "SCK_6") (pintype "bidirectional"))
      (node (ref "IC11") (pin "4") (pinfunction "SCK_4") (pintype "input"))
      (node (ref "IC4") (pin "10") (pinfunction "RB1/AN10/INT1/SCK/SCL_10") (pintype "bidirectional"))
      (node (ref "IC5") (pin "13") (pinfunction "SCK_13") (pintype "bidirectional"))
      (node (ref "IC6") (pin "49") (pinfunction "EMDIO/AEMDIO/RPD1/SCK1/RD1_49") (pintype "bidirectional"))
      (node (ref "IC8") (pin "2") (pinfunction "VL2_2") (pintype "bidirectional"))
    )
    (net (code "63") (name "/SPI_CLK_HI") (class "Default")
      (node (ref "IC12") (pin "10") (pinfunction "RB1/AN10/INT1/SCK/SCL_10") (pintype "bidirectional"))
      (node (ref "IC8") (pin "12") (pinfunction "VCC2_12") (pintype "bidirectional"))
    )
    (net (code "64") (name "/SPI_COUNTER") (class "Default")
      (node (ref "IC4") (pin "15") (pinfunction "RB5/KBI1/PGM_15") (pintype "bidirectional"))
      (node (ref "IC6") (pin "52") (pinfunction "*SQICS0/RPD4/PMWR/RD4_52") (pintype "bidirectional"))
    )
    (net (code "65") (name "/SPI_ETH") (class "Default")
      (node (ref "IC11") (pin "5") (pinfunction "~{CS}_5") (pintype "input"))
      (node (ref "IC4") (pin "44") (pinfunction "RC6/TX/CK_44") (pintype "bidirectional"))
    )
    (net (code "66") (name "/SPI_FLASH") (class "Default")
      (node (ref "IC10") (pin "1") (pinfunction "CE#_1") (pintype "bidirectional"))
      (node (ref "IC4") (pin "3") (pinfunction "RD5/SPP5/P1B_3") (pintype "bidirectional"))
    )
    (net (code "67") (name "/SPI_LCD") (class "Default")
      (node (ref "IC4") (pin "43") (pinfunction "RC5/D+/VP_43") (pintype "bidirectional"))
      (node (ref "IC8") (pin "6") (pinfunction "VL4_6") (pintype "bidirectional"))
    )
    (net (code "68") (name "/SPI_LCD_HI") (class "Default")
      (node (ref "IC12") (pin "14") (pinfunction "RB4/AN11/KBI0/CSSPP_14") (pintype "bidirectional"))
      (node (ref "IC8") (pin "8") (pinfunction "VCC4_8") (pintype "bidirectional"))
    )
    (net (code "69") (name "/SPI_SDI") (class "Default")
      (node (ref "IC10") (pin "2") (pinfunction "SO_2") (pintype "bidirectional"))
      (node (ref "IC11") (pin "2") (pinfunction "SO_2") (pintype "output"))
      (node (ref "IC4") (pin "9") (pinfunction "RB0/AN12/INT0/LFT0/SDI/SDA_9") (pintype "bidirectional"))
      (node (ref "IC5") (pin "15") (pinfunction "MISO_15") (pintype "bidirectional"))
      (node (ref "IC6") (pin "47") (pinfunction "SOSCI/RPC13/RC13_47") (pintype "bidirectional"))
      (node (ref "IC8") (pin "5") (pinfunction "VL3_5") (pintype "bidirectional"))
    )
    (net (code "70") (name "/SPI_SDI_HI") (class "Default")
      (node (ref "IC12") (pin "1") (pinfunction "RC7/RX/DT/SDO_1") (pintype "bidirectional"))
      (node (ref "IC8") (pin "9") (pinfunction "VCC3_9") (pintype "bidirectional"))
    )
    (net (code "71") (name "/SPI_SDO") (class "Default")
      (node (ref "IC10") (pin "5") (pinfunction "SI_5") (pintype "bidirectional"))
      (node (ref "IC11") (pin "3") (pinfunction "SI_3") (pintype "input"))
      (node (ref "IC4") (pin "1") (pinfunction "RC7/RX/DT/SDO_1") (pintype "bidirectional"))
      (node (ref "IC5") (pin "16") (pinfunction "MOSI_16") (pintype "bidirectional"))
      (node (ref "IC6") (pin "48") (pinfunction "SOSCO/RPC14/T1CK/RC14_48") (pintype "bidirectional"))
      (node (ref "IC8") (pin "1") (pinfunction "VL1_1") (pintype "bidirectional"))
    )
    (net (code "72") (name "/SPI_SDO_HI") (class "Default")
      (node (ref "IC12") (pin "9") (pinfunction "RB0/AN12/INT0/LFT0/SDI/SDA_9") (pintype "bidirectional"))
      (node (ref "IC8") (pin "13") (pinfunction "VCC1_13") (pintype "bidirectional"))
    )
    (net (code "73") (name "/SPI_USB") (class "Default")
      (node (ref "IC4") (pin "42") (pinfunction "RC4/D-/VM_42") (pintype "bidirectional"))
      (node (ref "IC5") (pin "14") (pinfunction "SS_14") (pintype "bidirectional"))
    )
    (net (code "74") (name "/STAT_LED") (class "Default")
      (node (ref "IC4") (pin "38") (pinfunction "RD0/SPP0_38") (pintype "bidirectional"))
      (node (ref "LED2") (pin "A") (pinfunction "A_A") (pintype "passive"))
    )
    (net (code "75") (name "/SW") (class "Default")
      (node (ref "D6") (pin "A") (pinfunction "A_A") (pintype "passive"))
      (node (ref "S1") (pin "1") (pinfunction "S_1") (pintype "passive"))
    )
    (net (code "76") (name "/SW1") (class "Default")
      (node (ref "IC3") (pin "3") (pinfunction "SW1_3") (pintype "input"))
      (node (ref "IC6") (pin "28") (pinfunction "TDI/AN8/RB13_28") (pintype "bidirectional"))
    )
    (net (code "77") (name "/SW2") (class "Default")
      (node (ref "IC3") (pin "6") (pinfunction "SW2_6") (pintype "input"))
      (node (ref "IC6") (pin "29") (pinfunction "AN9/RPB14/SCK3/PMA1/RB14_29") (pintype "bidirectional"))
    )
    (net (code "78") (name "/SW3") (class "Default")
      (node (ref "IC3") (pin "7") (pinfunction "SW3_7") (pintype "input"))
      (node (ref "IC6") (pin "30") (pinfunction "AN10/EMDC/AEMDC/RPB15/OCFB/PMA0/RB15_30") (pintype "bidirectional"))
    )
    (net (code "79") (name "/TPIN+") (class "Default")
      (node (ref "IC11") (pin "9") (pinfunction "TPIN+_9") (pintype "input"))
      (node (ref "R30") (pin "2") (pinfunction "2_2") (pintype "passive"))
      (node (ref "X4") (pin "7") (pinfunction "RD+_7") (pintype "input"))
    )
    (net (code "80") (name "/TPIN-") (class "Default")
      (node (ref "IC11") (pin "8") (pinfunction "TPIN-_8") (pintype "input"))
      (node (ref "R31") (pin "1") (pinfunction "1_1") (pintype "passive"))
      (node (ref "X4") (pin "8") (pinfunction "RD-_8") (pintype "input"))
    )
    (net (code "81") (name "/TPOUT+") (class "Default")
      (node (ref "IC11") (pin "13") (pinfunction "TPOUT+_13") (pintype "output"))
      (node (ref "R28") (pin "2") (pinfunction "2_2") (pintype "passive"))
      (node (ref "X4") (pin "1") (pinfunction "TD+_1") (pintype "input"))
    )
    (net (code "82") (name "/TPOUT-") (class "Default")
      (node (ref "IC11") (pin "12") (pinfunction "TPOUT-_12") (pintype "output"))
      (node (ref "R29") (pin "1") (pinfunction "1_1") (pintype "passive"))
      (node (ref "X4") (pin "2") (pinfunction "TD-_2") (pintype "input"))
    )
    (net (code "83") (name "/USB_D+") (class "Default")
      (node (ref "IC5") (pin "21") (pinfunction "D+_21") (pintype "bidirectional"))
      (node (ref "X1") (pin "3") (pinfunction "3_3") (pintype "input"))
    )
    (net (code "84") (name "/USB_D-") (class "Default")
      (node (ref "IC5") (pin "20") (pinfunction "D-_20") (pintype "bidirectional"))
      (node (ref "X1") (pin "2") (pinfunction "2_2") (pintype "input"))
    )
    (net (code "85") (name "/USB_PWR") (class "Default")
      (node (ref "LED4") (pin "A") (pinfunction "A_A") (pintype "passive"))
      (node (ref "X1") (pin "1") (pinfunction "1_1") (pintype "input"))
    )
    (net (code "86") (name "/VBUS") (class "Default")
      (node (ref "IC6") (pin "33") (pinfunction "VBUS_33") (pintype "power_in"))
    )
    (net (code "87") (name "GND") (class "Default")
      (node (ref "C10") (pin "2") (pinfunction "2_2") (pintype "passive"))
      (node (ref "C11") (pin "2") (pinfunction "2_2") (pintype "passive"))
      (node (ref "C12") (pin "2") (pinfunction "2_2") (pintype "passive"))
      (node (ref "C13") (pin "2") (pinfunction "2_2") (pintype "passive"))
      (node (ref "C17") (pin "2") (pinfunction "2_2") (pintype "passive"))
      (node (ref "C18") (pin "1") (pinfunction "1_1") (pintype "passive"))
      (node (ref "C20") (pin "1") (pinfunction "1_1") (pintype "passive"))
      (node (ref "C23") (pin "2") (pinfunction "2_2") (pintype "passive"))
      (node (ref "C24") (pin "2") (pinfunction "2_2") (pintype "passive"))
      (node (ref "C25") (pin "2") (pinfunction "2_2") (pintype "passive"))
      (node (ref "C26") (pin "2") (pinfunction "2_2") (pintype "passive"))
      (node (ref "C27") (pin "2") (pinfunction "2_2") (pintype "passive"))
      (node (ref "C28") (pin "2") (pinfunction "2_2") (pintype "passive"))
      (node (ref "C29") (pin "2") (pinfunction "2_2") (pintype "passive"))
      (node (ref "C3") (pin "2") (pinfunction "2_2") (pintype "passive"))
      (node (ref "C30") (pin "2") (pinfunction "2_2") (pintype "passive"))
      (node (ref "C31") (pin "2") (pinfunction "2_2") (pintype "passive"))
      (node (ref "C32") (pin "2") (pinfunction "2_2") (pintype "passive"))
      (node (ref "C33") (pin "2") (pinfunction "2_2") (pintype "passive"))
      (node (ref "C34") (pin "2") (pinfunction "2_2") (pintype "passive"))
      (node (ref "C35") (pin "2") (pinfunction "2_2") (pintype "passive"))
      (node (ref "C36") (pin "-") (pinfunction "-_-") (pintype "passive"))
      (node (ref "C37") (pin "2") (pinfunction "2_2") (pintype "passive"))
      (node (ref "C38") (pin "2") (pinfunction "2_2") (pintype "passive"))
      (node (ref "C39") (pin "2") (pinfunction "2_2") (pintype "passive"))
      (node (ref "C4") (pin "2") (pinfunction "2_2") (pintype "passive"))
      (node (ref "C40") (pin "2") (pinfunction "2_2") (pintype "passive"))
      (node (ref "C41") (pin "2") (pinfunction "2_2") (pintype "passive"))
      (node (ref "C42") (pin "2") (pinfunction "2_2") (pintype "passive"))
      (node (ref "C43") (pin "2") (pinfunction "2_2") (pintype "passive"))
      (node (ref "C44") (pin "2") (pinfunction "2_2") (pintype "passive"))
      (node (ref "C45") (pin "2") (pinfunction "2_2") (pintype "passive"))
      (node (ref "C46") (pin "2") (pinfunction "2_2") (pintype "passive"))
      (node (ref "C47") (pin "2") (pinfunction "2_2") (pintype "passive"))
      (node (ref "C50") (pin "2") (pinfunction "2_2") (pintype "passive"))
      (node (ref "C51") (pin "2") (pinfunction "2_2") (pintype "passive"))
      (node (ref "C52") (pin "2") (pinfunction "2_2") (pintype "passive"))
      (node (ref "C53") (pin "2") (pinfunction "2_2") (pintype "passive"))
      (node (ref "C6") (pin "2") (pinfunction "2_2") (pintype "passive"))
      (node (ref "C7") (pin "1") (pinfunction "1_1") (pintype "passive"))
      (node (ref "C8") (pin "-") (pinfunction "-_-") (pintype "passive"))
      (node (ref "C9") (pin "2") (pinfunction "2_2") (pintype "passive"))
      (node (ref "D1") (pin "A") (pinfunction "A_A") (pintype "passive"))
      (node (ref "D2") (pin "C") (pinfunction "C_C") (pintype "passive"))
      (node (ref "IC1") (pin "2") (pinfunction "GND_2") (pintype "passive"))
      (node (ref "IC1") (pin "3") (pinfunction "GND_3") (pintype "passive"))
      (node (ref "IC1") (pin "6") (pinfunction "GND_6") (pintype "passive"))
      (node (ref "IC1") (pin "7") (pinfunction "GND_7") (pintype "passive"))
      (node (ref "IC10") (pin "4") (pinfunction "GND_4") (pintype "power_in"))
      (node (ref "IC11") (pin "14") (pinfunction "VSSTX_14") (pintype "passive"))
      (node (ref "IC11") (pin "17") (pinfunction "VSSPLL_17") (pintype "passive"))
      (node (ref "IC11") (pin "18") (pinfunction "VSSOSC_18") (pintype "passive"))
      (node (ref "IC11") (pin "26") (pinfunction "VSS_26") (pintype "passive"))
      (node (ref "IC11") (pin "7") (pinfunction "VSSRX_7") (pintype "passive"))
      (node (ref "IC12") (pin "30") (pinfunction "VSS_30") (pintype "power_in"))
      (node (ref "IC12") (pin "31") (pinfunction "VSS_31") (pintype "power_in"))
      (node (ref "IC12") (pin "6") (pinfunction "VSS_6") (pintype "power_in"))
      (node (ref "IC12") (pin "EXP") (pinfunction "EXP_EXP") (pintype "passive"))
      (node (ref "IC2") (pin "2") (pinfunction "GND_2") (pintype "passive"))
      (node (ref "IC2") (pin "4") (pinfunction "GND_4") (pintype "passive"))
      (node (ref "IC3") (pin "5") (pinfunction "GND_5") (pintype "power_in"))
      (node (ref "IC4") (pin "30") (pinfunction "VSS_30") (pintype "power_in"))
      (node (ref "IC4") (pin "31") (pinfunction "VSS_31") (pintype "power_in"))
      (node (ref "IC4") (pin "6") (pinfunction "VSS_6") (pintype "power_in"))
      (node (ref "IC4") (pin "EXP") (pinfunction "EXP_EXP") (pintype "passive"))
      (node (ref "IC5") (pin "19") (pinfunction "GND_19") (pintype "bidirectional"))
      (node (ref "IC5") (pin "3") (pinfunction "GND_3") (pintype "bidirectional"))
      (node (ref "IC5") (pin "EXP") (pinfunction "EPAD_EXP") (pintype "bidirectional"))
      (node (ref "IC6") (pin "20") (pinfunction "AVSS_20") (pintype "power_in"))
      (node (ref "IC6") (pin "25") (pinfunction "VSS_3_25") (pintype "power_in"))
      (node (ref "IC6") (pin "34") (pinfunction "VUSB3V3_34") (pintype "power_in"))
      (node (ref "IC6") (pin "35") (pinfunction "VSS_4_35") (pintype "power_in"))
      (node (ref "IC6") (pin "40") (pinfunction "VSS_5_40") (pintype "power_in"))
      (node (ref "IC6") (pin "55") (pinfunction "VSS_6_55") (pintype "power_in"))
      (node (ref "IC6") (pin "59") (pinfunction "VSS_59") (pintype "power_in"))
      (node (ref "IC6") (pin "65") (pinfunction "EPAD_65") (pintype "passive"))
      (node (ref "IC6") (pin "7") (pinfunction "VSS_2_7") (pintype "power_in"))
      (node (ref "IC7") (pin "1") (pinfunction "CPGND_1") (pintype "bidirectional"))
      (node (ref "IC7") (pin "11") (pinfunction "AGND_11") (pintype "bidirectional"))
      (node (ref "IC7") (pin "15") (pinfunction "DGND_15") (pintype "bidirectional"))
      (node (ref "IC7") (pin "22") (pinfunction "AGND_22") (pintype "bidirectional"))
      (node (ref "IC7") (pin "3") (pinfunction "AGND_3") (pintype "bidirectional"))
      (node (ref "IC7") (pin "8") (pinfunction "AGND_8") (pintype "bidirectional"))
      (node (ref "IC7") (pin "EXP") (pinfunction "EXP_EXP") (pintype "bidirectional"))
      (node (ref "IC8") (pin "7") (pinfunction "GND_7") (pintype "power_in"))
      (node (ref "IC9") (pin "2") (pinfunction "GND_2") (pintype "passive"))
      (node (ref "IC9") (pin "4") (pinfunction "GND_4") (pintype "passive"))
      (node (ref "J1") (pin "1") (pinfunction "1_1") (pintype "passive"))
      (node (ref "J1") (pin "2") (pinfunction "2_2") (pintype "passive"))
      (node (ref "JP1") (pin "6") (pinfunction "6_6") (pintype "passive"))
      (node (ref "JP3") (pin "6") (pinfunction "6_6") (pintype "passive"))
      (node (ref "JP4") (pin "6") (pinfunction "6_6") (pintype "passive"))
      (node (ref "L1") (pin "2") (pinfunction "2_2") (pintype "passive"))
      (node (ref "L2") (pin "2") (pinfunction "2_2") (pintype "passive"))
      (node (ref "L3") (pin "2") (pinfunction "2_2") (pintype "passive"))
      (node (ref "L4") (pin "2") (pinfunction "2_2") (pintype "passive"))
      (node (ref "Q10") (pin "2") (pinfunction "2_2") (pintype "passive"))
      (node (ref "Q10") (pin "4") (pinfunction "4_4") (pintype "passive"))
      (node (ref "Q11") (pin "E") (pinfunction "E_E") (pintype "passive"))
      (node (ref "Q12") (pin "E") (pinfunction "E_E") (pintype "passive"))
      (node (ref "Q13") (pin "E") (pinfunction "E_E") (pintype "passive"))
      (node (ref "Q3") (pin "C") (pinfunction "C_C") (pintype "passive"))
      (node (ref "Q5") (pin "E") (pinfunction "E_E") (pintype "passive"))
      (node (ref "Q6") (pin "2") (pinfunction "GND_2") (pintype "power_in"))
      (node (ref "Q7") (pin "2") (pinfunction "2_2") (pintype "passive"))
      (node (ref "Q7") (pin "4") (pinfunction "4_4") (pintype "passive"))
      (node (ref "Q8") (pin "2") (pinfunction "2_2") (pintype "passive"))
      (node (ref "Q8") (pin "4") (pinfunction "4_4") (pintype "passive"))
      (node (ref "Q9") (pin "E") (pinfunction "E_E") (pintype "passive"))
      (node (ref "R11") (pin "2") (pinfunction "2_2") (pintype "passive"))
      (node (ref "R12") (pin "2") (pinfunction "2_2") (pintype "passive"))
      (node (ref "R14") (pin "2") (pinfunction "2_2") (pintype "passive"))
      (node (ref "R15") (pin "2") (pinfunction "2_2") (pintype "passive"))
      (node (ref "R17") (pin "2") (pinfunction "2_2") (pintype "passive"))
      (node (ref "R19") (pin "2") (pinfunction "2_2") (pintype "passive"))
      (node (ref "R2") (pin "2") (pinfunction "2_2") (pintype "passive"))
      (node (ref "R20") (pin "2") (pinfunction "2_2") (pintype "passive"))
      (node (ref "R21") (pin "2") (pinfunction "2_2") (pintype "passive"))
      (node (ref "R22") (pin "2") (pinfunction "2_2") (pintype "passive"))
      (node (ref "R24") (pin "2") (pinfunction "2_2") (pintype "passive"))
      (node (ref "R25") (pin "2") (pinfunction "2_2") (pintype "passive"))
      (node (ref "R26") (pin "2") (pinfunction "2_2") (pintype "passive"))
      (node (ref "R3") (pin "2") (pinfunction "2_2") (pintype "passive"))
      (node (ref "R34") (pin "3") (pinfunction "E_3") (pintype "passive"))
      (node (ref "R47") (pin "2") (pinfunction "2_2") (pintype "passive"))
      (node (ref "R48") (pin "2") (pinfunction "2_2") (pintype "passive"))
      (node (ref "R49") (pin "2") (pinfunction "2_2") (pintype "passive"))
      (node (ref "R50") (pin "2") (pinfunction "2_2") (pintype "passive"))
      (node (ref "R52") (pin "2") (pinfunction "2_2") (pintype "passive"))
      (node (ref "R8") (pin "1") (pinfunction "A_1") (pintype "passive"))
      (node (ref "R8") (pin "2") (pinfunction "S_2") (pintype "passive"))
      (node (ref "T1") (pin "P$2") (pinfunction "P$2_P$2") (pintype "passive"))
      (node (ref "T1") (pin "P$6") (pinfunction "P$6_P$6") (pintype "passive"))
      (node (ref "X1") (pin "5") (pinfunction "5_5") (pintype "input"))
      (node (ref "X1") (pin "M1") (pinfunction "S1_M1") (pintype "passive"))
      (node (ref "X1") (pin "M2") (pinfunction "S2_M2") (pintype "passive"))
      (node (ref "X1") (pin "M3") (pinfunction "S3_M3") (pintype "passive"))
      (node (ref "X1") (pin "M4") (pinfunction "S4_M4") (pintype "passive"))
      (node (ref "X2") (pin "2") (pinfunction "2_2") (pintype "passive"))
      (node (ref "X2") (pin "3") (pinfunction "2_3") (pintype "passive"))
      (node (ref "X2") (pin "4") (pinfunction "2_4") (pintype "passive"))
      (node (ref "X2") (pin "5") (pinfunction "2_5") (pintype "passive"))
      (node (ref "X3") (pin "2") (pinfunction "2_2") (pintype "passive"))
      (node (ref "X3") (pin "3") (pinfunction "2_3") (pintype "passive"))
      (node (ref "X3") (pin "4") (pinfunction "2_4") (pintype "passive"))
      (node (ref "X3") (pin "5") (pinfunction "2_5") (pintype "passive"))
      (node (ref "X4") (pin "10") (pinfunction "C-R_10") (pintype "passive"))
      (node (ref "X4") (pin "11") (pinfunction "C-L_11") (pintype "passive"))
      (node (ref "X5") (pin "1") (pinfunction "1_1") (pintype "passive"))
      (node (ref "X5") (pin "20") (pinfunction "1_20") (pintype "passive"))
      (node (ref "X6") (pin "1") (pinfunction "1_1") (pintype "passive"))
      (node (ref "X7") (pin "2") (pinfunction "2_2") (pintype "passive"))
      (node (ref "X7") (pin "3") (pinfunction "2_3") (pintype "passive"))
      (node (ref "X7") (pin "4") (pinfunction "2_4") (pintype "passive"))
      (node (ref "X7") (pin "5") (pinfunction "2_5") (pintype "passive"))
    )
    (net (code "88") (name "Net-(C1-Pad2)") (class "Default")
      (node (ref "C1") (pin "2") (pinfunction "2_2") (pintype "passive"))
      (node (ref "C2") (pin "1") (pinfunction "1_1") (pintype "passive"))
      (node (ref "R1") (pin "2") (pinfunction "2_2") (pintype "passive"))
    )
    (net (code "89") (name "Net-(C5-Pad1)") (class "Default")
      (node (ref "C5") (pin "1") (pinfunction "1_1") (pintype "passive"))
      (node (ref "D3") (pin "A") (pinfunction "A_A") (pintype "passive"))
      (node (ref "Q3") (pin "B") (pinfunction "B_B") (pintype "passive"))
      (node (ref "R6") (pin "1") (pinfunction "1_1") (pintype "passive"))
      (node (ref "R7") (pin "2") (pinfunction "2_2") (pintype "passive"))
    )
    (net (code "90") (name "Net-(C5-Pad2)") (class "Default")
      (node (ref "C5") (pin "2") (pinfunction "2_2") (pintype "passive"))
      (node (ref "Q2") (pin "C") (pinfunction "C_C") (pintype "passive"))
      (node (ref "R4") (pin "1") (pinfunction "1_1") (pintype "passive"))
    )
    (net (code "91") (name "Net-(C7-Pad2)") (class "Default")
      (node (ref "C7") (pin "2") (pinfunction "2_2") (pintype "passive"))
      (node (ref "Q4") (pin "B") (pinfunction "B_B") (pintype "passive"))
      (node (ref "R10") (pin "2") (pinfunction "2_2") (pintype "passive"))
      (node (ref "R11") (pin "1") (pinfunction "1_1") (pintype "passive"))
      (node (ref "R13") (pin "2") (pinfunction "2_2") (pintype "passive"))
    )
    (net (code "92") (name "Net-(C15-Pad2)") (class "Default")
      (node (ref "C15") (pin "2") (pinfunction "2_2") (pintype "passive"))
      (node (ref "C16") (pin "1") (pinfunction "1_1") (pintype "passive"))
      (node (ref "R20") (pin "1") (pinfunction "1_1") (pintype "passive"))
    )
    (net (code "93") (name "Net-(C19-Pad1)") (class "Default")
      (node (ref "C19") (pin "1") (pinfunction "1_1") (pintype "passive"))
      (node (ref "R22") (pin "1") (pinfunction "1_1") (pintype "passive"))
    )
    (net (code "94") (name "Net-(D4-PadA)") (class "Default")
      (node (ref "D4") (pin "A") (pinfunction "A_A") (pintype "passive"))
      (node (ref "D5") (pin "A") (pinfunction "A_A") (pintype "passive"))
      (node (ref "Q4") (pin "C") (pinfunction "C_C") (pintype "passive"))
      (node (ref "R12") (pin "1") (pinfunction "1_1") (pintype "passive"))
    )
    (net (code "95") (name "Net-(D4-PadC)") (class "Default")
      (node (ref "D4") (pin "C") (pinfunction "C_C") (pintype "passive"))
      (node (ref "Q5") (pin "C") (pinfunction "C_C") (pintype "passive"))
      (node (ref "R13") (pin "1") (pinfunction "1_1") (pintype "passive"))
      (node (ref "R16") (pin "2") (pinfunction "2_2") (pintype "passive"))
      (node (ref "R18") (pin "2") (pinfunction "2_2") (pintype "passive"))
    )
    (net (code "96") (name "Net-(D5-PadC)") (class "Default")
      (node (ref "D5") (pin "C") (pinfunction "C_C") (pintype "passive"))
      (node (ref "Q5") (pin "B") (pinfunction "B_B") (pintype "passive"))
      (node (ref "R14") (pin "1") (pinfunction "1_1") (pintype "passive"))
    )
    (net (code "97") (name "Net-(D7-A1)") (class "Default")
      (node (ref "D7") (pin "1") (pinfunction "A1_1") (pintype "passive"))
      (node (ref "K2") (pin "1") (pinfunction "+_1") (pintype "passive"))
      (node (ref "Q9") (pin "C") (pinfunction "C_C") (pintype "passive"))
      (node (ref "R39") (pin "2") (pinfunction "2_2") (pintype "passive"))
    )
    (net (code "98") (name "Net-(D7-A2)") (class "Default")
      (node (ref "D7") (pin "2") (pinfunction "A2_2") (pintype "passive"))
      (node (ref "K2") (pin "8") (pinfunction "-_8") (pintype "passive"))
      (node (ref "Q11") (pin "C") (pinfunction "C_C") (pintype "passive"))
      (node (ref "R40") (pin "2") (pinfunction "2_2") (pintype "passive"))
    )
    (net (code "99") (name "Net-(D8-A1)") (class "Default")
      (node (ref "D8") (pin "1") (pinfunction "A1_1") (pintype "passive"))
      (node (ref "K1") (pin "1") (pinfunction "+_1") (pintype "passive"))
      (node (ref "Q12") (pin "C") (pinfunction "C_C") (pintype "passive"))
      (node (ref "R41") (pin "2") (pinfunction "2_2") (pintype "passive"))
    )
    (net (code "100") (name "Net-(D8-A2)") (class "Default")
      (node (ref "D8") (pin "2") (pinfunction "A2_2") (pintype "passive"))
      (node (ref "K1") (pin "8") (pinfunction "-_8") (pintype "passive"))
      (node (ref "Q13") (pin "C") (pinfunction "C_C") (pintype "passive"))
      (node (ref "R42") (pin "2") (pinfunction "2_2") (pintype "passive"))
    )
    (net (code "101") (name "Net-(IC1-VI)") (class "Default")
      (node (ref "C8") (pin "+") (pinfunction "+_+") (pintype "passive"))
      (node (ref "D6") (pin "C") (pinfunction "C_C") (pintype "passive"))
      (node (ref "IC1") (pin "8") (pinfunction "VI_8") (pintype "input"))
    )
    (net (code "102") (name "Net-(IC3-~{IN})") (class "Default")
      (node (ref "C13") (pin "1") (pinfunction "1_1") (pintype "passive"))
      (node (ref "IC3") (pin "8") (pinfunction "~{IN}_8") (pintype "input"))
    )
    (net (code "103") (name "Net-(IC4-OSC1{slash}CLKI)") (class "Default")
      (node (ref "C45") (pin "1") (pinfunction "1_1") (pintype "passive"))
      (node (ref "IC4") (pin "32") (pinfunction "OSC1/CLKI_32") (pintype "input"))
      (node (ref "Q8") (pin "1") (pinfunction "1_1") (pintype "passive"))
    )
    (net (code "104") (name "Net-(IC4-RA6{slash}OSC2{slash}CLKO)") (class "Default")
      (node (ref "C46") (pin "1") (pinfunction "1_1") (pintype "passive"))
      (node (ref "IC4") (pin "33") (pinfunction "RA6/OSC2/CLKO_33") (pintype "output"))
      (node (ref "Q8") (pin "3") (pinfunction "3_3") (pintype "passive"))
    )
    (net (code "105") (name "Net-(IC7-CC)") (class "Default")
      (node (ref "C17") (pin "1") (pinfunction "1_1") (pintype "passive"))
      (node (ref "IC7") (pin "12") (pinfunction "CC_12") (pintype "bidirectional"))
    )
    (net (code "106") (name "Net-(IC7-CN)") (class "Default")
      (node (ref "C14") (pin "1") (pinfunction "1_1") (pintype "passive"))
      (node (ref "IC7") (pin "14") (pinfunction "CN_14") (pintype "bidirectional"))
    )
    (net (code "107") (name "Net-(IC7-CP)") (class "Default")
      (node (ref "C18") (pin "2") (pinfunction "2_2") (pintype "passive"))
      (node (ref "C19") (pin "2") (pinfunction "2_2") (pintype "passive"))
      (node (ref "IC7") (pin "24") (pinfunction "CP_24") (pintype "bidirectional"))
      (node (ref "R23") (pin "2") (pinfunction "2_2") (pintype "passive"))
    )
    (net (code "108") (name "Net-(IC7-L1)") (class "Default")
      (node (ref "IC7") (pin "9") (pinfunction "L1_9") (pintype "bidirectional"))
      (node (ref "L1") (pin "1") (pinfunction "1_1") (pintype "passive"))
      (node (ref "R25") (pin "1") (pinfunction "1_1") (pintype "passive"))
    )
    (net (code "109") (name "Net-(IC7-L2)") (class "Default")
      (node (ref "IC7") (pin "10") (pinfunction "L2_10") (pintype "bidirectional"))
      (node (ref "L2") (pin "1") (pinfunction "1_1") (pintype "passive"))
      (node (ref "R24") (pin "1") (pinfunction "1_1") (pintype "passive"))
    )
    (net (code "110") (name "Net-(IC7-REFIN)") (class "Default")
      (node (ref "C15") (pin "1") (pinfunction "1_1") (pintype "passive"))
      (node (ref "IC7") (pin "16") (pinfunction "REFIN_16") (pintype "bidirectional"))
    )
    (net (code "111") (name "Net-(IC7-RFOUTA)") (class "Default")
      (node (ref "C21") (pin "1") (pinfunction "1_1") (pintype "passive"))
      (node (ref "IC7") (pin "4") (pinfunction "RFOUTA_4") (pintype "bidirectional"))
      (node (ref "L4") (pin "1") (pinfunction "1_1") (pintype "passive"))
    )
    (net (code "112") (name "Net-(IC7-RFOUTB)") (class "Default")
      (node (ref "C22") (pin "2") (pinfunction "2_2") (pintype "passive"))
      (node (ref "IC7") (pin "5") (pinfunction "RFOUTB_5") (pintype "bidirectional"))
      (node (ref "L3") (pin "1") (pinfunction "1_1") (pintype "passive"))
    )
    (net (code "113") (name "Net-(IC7-RSET)") (class "Default")
      (node (ref "IC7") (pin "13") (pinfunction "RSET_13") (pintype "bidirectional"))
      (node (ref "R21") (pin "1") (pinfunction "1_1") (pintype "passive"))
    )
    (net (code "114") (name "Net-(IC7-VTUNE)") (class "Default")
      (node (ref "C20") (pin "2") (pinfunction "2_2") (pintype "passive"))
      (node (ref "IC7") (pin "7") (pinfunction "VTUNE_7") (pintype "bidirectional"))
      (node (ref "R23") (pin "1") (pinfunction "1_1") (pintype "passive"))
    )
    (net (code "115") (name "Net-(IC11-RBIAS)") (class "Default")
      (node (ref "IC11") (pin "10") (pinfunction "RBIAS_10") (pintype "input"))
      (node (ref "R26") (pin "1") (pinfunction "1_1") (pintype "passive"))
    )
    (net (code "116") (name "Net-(IC11-VCAP)") (class "Default")
      (node (ref "C36") (pin "+") (pinfunction "+_+") (pintype "passive"))
      (node (ref "IC11") (pin "25") (pinfunction "VCAP_25") (pintype "power_in"))
    )
    (net (code "117") (name "Net-(IC11-~{RESET})") (class "Default")
      (node (ref "IC11") (pin "6") (pinfunction "~{RESET}_6") (pintype "input"))
      (node (ref "R27") (pin "1") (pinfunction "1_1") (pintype "passive"))
    )
    (net (code "118") (name "Net-(IC12-OSC1{slash}CLKI)") (class "Default")
      (node (ref "C52") (pin "1") (pinfunction "1_1") (pintype "passive"))
      (node (ref "IC12") (pin "32") (pinfunction "OSC1/CLKI_32") (pintype "input"))
      (node (ref "Q10") (pin "1") (pinfunction "1_1") (pintype "passive"))
    )
    (net (code "119") (name "Net-(IC12-RA6{slash}OSC2{slash}CLKO)") (class "Default")
      (node (ref "C53") (pin "1") (pinfunction "1_1") (pintype "passive"))
      (node (ref "IC12") (pin "33") (pinfunction "RA6/OSC2/CLKO_33") (pintype "output"))
      (node (ref "Q10") (pin "3") (pinfunction "3_3") (pintype "passive"))
    )
    (net (code "120") (name "Net-(K2B-P)") (class "Default")
      (node (ref "K2") (pin "6") (pinfunction "P_6") (pintype "passive"))
      (node (ref "R15") (pin "1") (pinfunction "1_1") (pintype "passive"))
      (node (ref "R17") (pin "1") (pinfunction "1_1") (pintype "passive"))
    )
    (net (code "121") (name "Net-(K2B-S)") (class "Default")
      (node (ref "C2") (pin "2") (pinfunction "2_2") (pintype "passive"))
      (node (ref "D1") (pin "C") (pinfunction "C_C") (pintype "passive"))
      (node (ref "D2") (pin "A") (pinfunction "A_A") (pintype "passive"))
      (node (ref "K2") (pin "5") (pinfunction "S_5") (pintype "passive"))
      (node (ref "Q1") (pin "3") (pinfunction "G_3") (pintype "passive"))
      (node (ref "R1") (pin "1") (pinfunction "1_1") (pintype "passive"))
      (node (ref "R2") (pin "1") (pinfunction "1_1") (pintype "passive"))
    )
    (net (code "122") (name "Net-(LED1-PadC)") (class "Default")
      (node (ref "LED1") (pin "C") (pinfunction "C_C") (pintype "passive"))
      (node (ref "R47") (pin "1") (pinfunction "1_1") (pintype "passive"))
    )
    (net (code "123") (name "Net-(LED2-PadC)") (class "Default")
      (node (ref "LED2") (pin "C") (pinfunction "C_C") (pintype "passive"))
      (node (ref "R48") (pin "1") (pinfunction "1_1") (pintype "passive"))
    )
    (net (code "124") (name "Net-(LED3-PadC)") (class "Default")
      (node (ref "LED3") (pin "C") (pinfunction "C_C") (pintype "passive"))
      (node (ref "R49") (pin "1") (pinfunction "1_1") (pintype "passive"))
    )
    (net (code "125") (name "Net-(LED4-PadC)") (class "Default")
      (node (ref "LED4") (pin "C") (pinfunction "C_C") (pintype "passive"))
      (node (ref "R50") (pin "1") (pinfunction "1_1") (pintype "passive"))
    )
    (net (code "126") (name "Net-(Q1-D)") (class "Default")
      (node (ref "Q1") (pin "1") (pinfunction "D_1") (pintype "passive"))
      (node (ref "Q2") (pin "B") (pinfunction "B_B") (pintype "passive"))
      (node (ref "R5") (pin "2") (pinfunction "S_2") (pintype "passive"))
      (node (ref "R5") (pin "3") (pinfunction "E_3") (pintype "passive"))
    )
    (net (code "127") (name "Net-(Q1-S)") (class "Default")
      (node (ref "C3") (pin "1") (pinfunction "1_1") (pintype "passive"))
      (node (ref "Q1") (pin "2") (pinfunction "S_2") (pintype "passive"))
      (node (ref "R3") (pin "1") (pinfunction "1_1") (pintype "passive"))
      (node (ref "R4") (pin "2") (pinfunction "2_2") (pintype "passive"))
    )
    (net (code "128") (name "Net-(Q3-PadE)") (class "Default")
      (node (ref "Q3") (pin "E") (pinfunction "E_E") (pintype "passive"))
      (node (ref "Q4") (pin "E") (pinfunction "E_E") (pintype "passive"))
      (node (ref "R9") (pin "2") (pinfunction "2_2") (pintype "passive"))
    )
    (net (code "129") (name "Net-(Q9-PadB)") (class "Default")
      (node (ref "Q9") (pin "B") (pinfunction "B_B") (pintype "passive"))
      (node (ref "R46") (pin "1") (pinfunction "1_1") (pintype "passive"))
    )
    (net (code "130") (name "Net-(Q11-PadB)") (class "Default")
      (node (ref "Q11") (pin "B") (pinfunction "B_B") (pintype "passive"))
      (node (ref "R45") (pin "2") (pinfunction "2_2") (pintype "passive"))
    )
    (net (code "131") (name "Net-(Q12-PadB)") (class "Default")
      (node (ref "Q12") (pin "B") (pinfunction "B_B") (pintype "passive"))
      (node (ref "R44") (pin "2") (pinfunction "2_2") (pintype "passive"))
    )
    (net (code "132") (name "Net-(Q13-PadB)") (class "Default")
      (node (ref "Q13") (pin "B") (pinfunction "B_B") (pintype "passive"))
      (node (ref "R43") (pin "2") (pinfunction "2_2") (pintype "passive"))
    )
    (net (code "133") (name "Net-(R8-E)") (class "Default")
      (node (ref "R6") (pin "2") (pinfunction "2_2") (pintype "passive"))
      (node (ref "R8") (pin "3") (pinfunction "E_3") (pintype "passive"))
    )
    (net (code "134") (name "Net-(R34-A)") (class "Default")
      (node (ref "R34") (pin "1") (pinfunction "A_1") (pintype "passive"))
      (node (ref "X5") (pin "18") (pinfunction "1_18") (pintype "passive"))
    )
    (net (code "135") (name "Net-(R34-S)") (class "Default")
      (node (ref "R34") (pin "2") (pinfunction "S_2") (pintype "passive"))
      (node (ref "X5") (pin "3") (pinfunction "1_3") (pintype "passive"))
    )
    (net (code "136") (name "Net-(X4-A-L)") (class "Default")
      (node (ref "R33") (pin "1") (pinfunction "1_1") (pintype "passive"))
      (node (ref "X4") (pin "12") (pinfunction "A-L_12") (pintype "passive"))
    )
    (net (code "137") (name "Net-(X4-A-R)") (class "Default")
      (node (ref "R32") (pin "1") (pinfunction "1_1") (pintype "passive"))
      (node (ref "X4") (pin "9") (pinfunction "A-R_9") (pintype "passive"))
    )
    (net (code "138") (name "Net-(X4-CR)") (class "Default")
      (node (ref "C44") (pin "1") (pinfunction "1_1") (pintype "passive"))
      (node (ref "R30") (pin "1") (pinfunction "1_1") (pintype "passive"))
      (node (ref "R31") (pin "2") (pinfunction "2_2") (pintype "passive"))
      (node (ref "X4") (pin "6") (pinfunction "CR_6") (pintype "input"))
    )
    (net (code "139") (name "Net-(X4-CT)") (class "Default")
      (node (ref "C43") (pin "1") (pinfunction "1_1") (pintype "passive"))
      (node (ref "L5") (pin "2") (pinfunction "2_2") (pintype "passive"))
      (node (ref "R28") (pin "1") (pinfunction "1_1") (pintype "passive"))
      (node (ref "R29") (pin "2") (pinfunction "2_2") (pintype "passive"))
      (node (ref "X4") (pin "3") (pinfunction "CT_3") (pintype "input"))
    )
    (net (code "140") (name "Net-(X5K-1)") (class "Default")
      (node (ref "R38") (pin "1") (pinfunction "1_1") (pintype "passive"))
      (node (ref "X5") (pin "19") (pinfunction "1_19") (pintype "passive"))
    )
    (net (code "141") (name "unconnected-(D7-C-Pad3)") (class "Default")
      (node (ref "D7") (pin "3") (pinfunction "C_3") (pintype "passive"))
    )
    (net (code "142") (name "unconnected-(D8-C-Pad3)") (class "Default")
      (node (ref "D8") (pin "3") (pinfunction "C_3") (pintype "passive"))
    )
    (net (code "143") (name "unconnected-(IC4-NC-Pad13)") (class "Default")
      (node (ref "IC4") (pin "13") (pinfunction "NC_13") (pintype "bidirectional"))
    )
    (net (code "144") (name "unconnected-(IC4-RA0{slash}AN0-Pad19)") (class "Default")
      (node (ref "IC4") (pin "19") (pinfunction "RA0/AN0_19") (pintype "bidirectional"))
    )
    (net (code "145") (name "unconnected-(IC4-RA1{slash}AN1-Pad20)") (class "Default")
      (node (ref "IC4") (pin "20") (pinfunction "RA1/AN1_20") (pintype "bidirectional"))
    )
    (net (code "146") (name "unconnected-(IC4-RA2{slash}AN2{slash}VREF-{slash}CVREF-Pad21)") (class "Default")
      (node (ref "IC4") (pin "21") (pinfunction "RA2/AN2/VREF-/CVREF_21") (pintype "bidirectional"))
    )
    (net (code "147") (name "unconnected-(IC4-RA3{slash}AN3{slash}VREF+-Pad22)") (class "Default")
      (node (ref "IC4") (pin "22") (pinfunction "RA3/AN3/VREF+_22") (pintype "bidirectional"))
    )
    (net (code "148") (name "unconnected-(IC4-RA4{slash}T0CKI{slash}CIOUT{slash}RCV-Pad23)") (class "Default")
      (node (ref "IC4") (pin "23") (pinfunction "RA4/T0CKI/CIOUT/RCV_23") (pintype "bidirectional"))
    )
    (net (code "149") (name "unconnected-(IC4-RB4{slash}AN11{slash}KBI0{slash}CSSPP-Pad14)") (class "Default")
      (node (ref "IC4") (pin "14") (pinfunction "RB4/AN11/KBI0/CSSPP_14") (pintype "bidirectional"))
    )
    (net (code "150") (name "unconnected-(IC4-RC2{slash}CCP1{slash}P1A-Pad36)") (class "Default")
      (node (ref "IC4") (pin "36") (pinfunction "RC2/CCP1/P1A_36") (pintype "bidirectional"))
    )
    (net (code "151") (name "unconnected-(IC4-RD2{slash}SPP2-Pad40)") (class "Default")
      (node (ref "IC4") (pin "40") (pinfunction "RD2/SPP2_40") (pintype "bidirectional"))
    )
    (net (code "152") (name "unconnected-(IC4-RD3{slash}SPP3-Pad41)") (class "Default")
      (node (ref "IC4") (pin "41") (pinfunction "RD3/SPP3_41") (pintype "bidirectional"))
    )
    (net (code "153") (name "unconnected-(IC4-RD4{slash}SPP4-Pad2)") (class "Default")
      (node (ref "IC4") (pin "2") (pinfunction "RD4/SPP4_2") (pintype "bidirectional"))
    )
    (net (code "154") (name "unconnected-(IC4-VUSB-Pad37)") (class "Default")
      (node (ref "IC4") (pin "37") (pinfunction "VUSB_37") (pintype "bidirectional"))
    )
    (net (code "155") (name "unconnected-(IC5-GOUT0-Pad4)") (class "Default")
      (node (ref "IC5") (pin "4") (pinfunction "GOUT0_4") (pintype "bidirectional"))
    )
    (net (code "156") (name "unconnected-(IC5-GOUT1-Pad5)") (class "Default")
      (node (ref "IC5") (pin "5") (pinfunction "GOUT1_5") (pintype "bidirectional"))
    )
    (net (code "157") (name "unconnected-(IC5-GOUT2-Pad6)") (class "Default")
      (node (ref "IC5") (pin "6") (pinfunction "GOUT2_6") (pintype "bidirectional"))
    )
    (net (code "158") (name "unconnected-(IC5-GOUT3-Pad7)") (class "Default")
      (node (ref "IC5") (pin "7") (pinfunction "GOUT3_7") (pintype "bidirectional"))
    )
    (net (code "159") (name "unconnected-(IC5-GOUT4-Pad8)") (class "Default")
      (node (ref "IC5") (pin "8") (pinfunction "GOUT4_8") (pintype "bidirectional"))
    )
    (net (code "160") (name "unconnected-(IC5-GOUT5-Pad9)") (class "Default")
      (node (ref "IC5") (pin "9") (pinfunction "GOUT5_9") (pintype "bidirectional"))
    )
    (net (code "161") (name "unconnected-(IC5-GOUT6-Pad10)") (class "Default")
      (node (ref "IC5") (pin "10") (pinfunction "GOUT6_10") (pintype "bidirectional"))
    )
    (net (code "162") (name "unconnected-(IC5-GOUT7-Pad11)") (class "Default")
      (node (ref "IC5") (pin "11") (pinfunction "GOUT7_11") (pintype "bidirectional"))
    )
    (net (code "163") (name "unconnected-(IC5-GPIN0-Pad26)") (class "Default")
      (node (ref "IC5") (pin "26") (pinfunction "GPIN0_26") (pintype "bidirectional"))
    )
    (net (code "164") (name "unconnected-(IC5-GPIN1-Pad27)") (class "Default")
      (node (ref "IC5") (pin "27") (pinfunction "GPIN1_27") (pintype "bidirectional"))
    )
    (net (code "165") (name "unconnected-(IC5-GPIN2-Pad28)") (class "Default")
      (node (ref "IC5") (pin "28") (pinfunction "GPIN2_28") (pintype "bidirectional"))
    )
    (net (code "166") (name "unconnected-(IC5-GPIN3-Pad29)") (class "Default")
      (node (ref "IC5") (pin "29") (pinfunction "GPIN3_29") (pintype "bidirectional"))
    )
    (net (code "167") (name "unconnected-(IC5-GPIN4-Pad30)") (class "Default")
      (node (ref "IC5") (pin "30") (pinfunction "GPIN4_30") (pintype "bidirectional"))
    )
    (net (code "168") (name "unconnected-(IC5-GPIN5-Pad31)") (class "Default")
      (node (ref "IC5") (pin "31") (pinfunction "GPIN5_31") (pintype "bidirectional"))
    )
    (net (code "169") (name "unconnected-(IC5-GPIN6-Pad32)") (class "Default")
      (node (ref "IC5") (pin "32") (pinfunction "GPIN6_32") (pintype "bidirectional"))
    )
    (net (code "170") (name "unconnected-(IC5-GPIN7-Pad1)") (class "Default")
      (node (ref "IC5") (pin "1") (pinfunction "GPIN7_1") (pintype "bidirectional"))
    )
    (net (code "171") (name "unconnected-(IC5-GPX-Pad17)") (class "Default")
      (node (ref "IC5") (pin "17") (pinfunction "GPX_17") (pintype "bidirectional"))
    )
    (net (code "172") (name "unconnected-(IC5-INT-Pad18)") (class "Default")
      (node (ref "IC5") (pin "18") (pinfunction "INT_18") (pintype "bidirectional"))
    )
    (net (code "173") (name "unconnected-(IC5-RES-Pad12)") (class "Default")
      (node (ref "IC5") (pin "12") (pinfunction "RES_12") (pintype "bidirectional"))
    )
    (net (code "174") (name "unconnected-(IC5-VBCOMP-Pad22)") (class "Default")
      (node (ref "IC5") (pin "22") (pinfunction "VBCOMP_22") (pintype "bidirectional"))
    )
    (net (code "175") (name "unconnected-(IC5-VL-Pad2)") (class "Default")
      (node (ref "IC5") (pin "2") (pinfunction "VL_2") (pintype "bidirectional"))
    )
    (net (code "176") (name "unconnected-(IC5-X0-Pad25)") (class "Default")
      (node (ref "IC5") (pin "25") (pinfunction "X0_25") (pintype "bidirectional"))
    )
    (net (code "177") (name "unconnected-(IC5-X1-Pad24)") (class "Default")
      (node (ref "IC5") (pin "24") (pinfunction "X1_24") (pintype "bidirectional"))
    )
    (net (code "178") (name "unconnected-(IC6-*SQICS1{slash}RPD5{slash}PMRD{slash}RD5-Pad53)") (class "Default")
      (node (ref "IC6") (pin "53") (pinfunction "*SQICS1/RPD5/PMRD/RD5_53") (pintype "bidirectional"))
    )
    (net (code "179") (name "unconnected-(IC6-AERXCLK{slash}AEREFCLK{slash}ECRS{slash}RPD11{slash}PMCS1{slash}PMA14{slash}RD11-Pad45)") (class "Default")
      (node (ref "IC6") (pin "45") (pinfunction "AERXCLK/AEREFCLK/ECRS/RPD11/PMCS1/PMA14/RD11_45") (pintype "bidirectional"))
    )
    (net (code "180") (name "unconnected-(IC6-AERXD0{slash}ETXD2{slash}RPD9{slash}SDA1{slash}PMCS2{slash}PMA15{slash}RD9-Pad43)") (class "Default")
      (node (ref "IC6") (pin "43") (pinfunction "AERXD0/ETXD2/RPD9/SDA1/PMCS2/PMA15/RD9_43") (pintype "bidirectional"))
    )
    (net (code "181") (name "unconnected-(IC6-AERXD1{slash}ETXD3{slash}RPD0{slash}RTCC{slash}INT0{slash}RD0-Pad46)") (class "Default")
      (node (ref "IC6") (pin "46") (pinfunction "AERXD1/ETXD3/RPD0/RTCC/INT0/RD0_46") (pintype "bidirectional"))
    )
    (net (code "182") (name "unconnected-(IC6-AERXERR{slash}ETXCLK{slash}RPD3{slash}SCL3{slash}RD3-Pad51)") (class "Default")
      (node (ref "IC6") (pin "51") (pinfunction "AERXERR/ETXCLK/RPD3/SCL3/RD3_51") (pintype "bidirectional"))
    )
    (net (code "183") (name "unconnected-(IC6-AN2{slash}C2INB{slash}RPB2{slash}RB2-Pad14)") (class "Default")
      (node (ref "IC6") (pin "14") (pinfunction "AN2/C2INB/RPB2/RB2_14") (pintype "bidirectional"))
    )
    (net (code "184") (name "unconnected-(IC6-AN3{slash}C2INA{slash}RPB3{slash}RB3-Pad13)") (class "Default")
      (node (ref "IC6") (pin "13") (pinfunction "AN3/C2INA/RPB3/RB3_13") (pintype "bidirectional"))
    )
    (net (code "185") (name "unconnected-(IC6-AN4{slash}C1INB{slash}RB4-Pad12)") (class "Default")
      (node (ref "IC6") (pin "12") (pinfunction "AN4/C1INB/RB4_12") (pintype "bidirectional"))
    )
    (net (code "186") (name "unconnected-(IC6-AN11{slash}C2INC{slash}RPG9{slash}PMA2{slash}RG9-Pad10)") (class "Default")
      (node (ref "IC6") (pin "10") (pinfunction "AN11/C2INC/RPG9/PMA2/RG9_10") (pintype "bidirectional"))
    )
    (net (code "187") (name "unconnected-(IC6-AN12{slash}C2IND{slash}RPG8{slash}SCL4{slash}PMA3{slash}RG8-Pad6)") (class "Default")
      (node (ref "IC6") (pin "6") (pinfunction "AN12/C2IND/RPG8/SCL4/PMA3/RG8_6") (pintype "bidirectional"))
    )
    (net (code "188") (name "unconnected-(IC6-AN13{slash}C1INC{slash}RPG7{slash}SDA4{slash}PMA4{slash}RG7-Pad5)") (class "Default")
      (node (ref "IC6") (pin "5") (pinfunction "AN13/C1INC/RPG7/SDA4/PMA4/RG7_5") (pintype "bidirectional"))
    )
    (net (code "189") (name "unconnected-(IC6-AN14{slash}C1IND{slash}RPG6{slash}SCK2{slash}PMA5{slash}RG6-Pad4)") (class "Default")
      (node (ref "IC6") (pin "4") (pinfunction "AN14/C1IND/RPG6/SCK2/PMA5/RG6_4") (pintype "bidirectional"))
    )
    (net (code "190") (name "unconnected-(IC6-AN15{slash}ETXD1{slash}PMD7{slash}RE7-Pad3)") (class "Default")
      (node (ref "IC6") (pin "3") (pinfunction "AN15/ETXD1/PMD7/RE7_3") (pintype "bidirectional"))
    )
    (net (code "191") (name "unconnected-(IC6-AN16{slash}ETXD0{slash}PMD6{slash}RE6-Pad2)") (class "Default")
      (node (ref "IC6") (pin "2") (pinfunction "AN16/ETXD0/PMD6/RE6_2") (pintype "bidirectional"))
    )
    (net (code "192") (name "unconnected-(IC6-AN17{slash}ETXEN{slash}RPE5{slash}PMD5{slash}RE5-Pad1)") (class "Default")
      (node (ref "IC6") (pin "1") (pinfunction "AN17/ETXEN/RPE5/PMD5/RE5_1") (pintype "bidirectional"))
    )
    (net (code "193") (name "unconnected-(IC6-AN18{slash}ERXERR{slash}PMD4{slash}RE4-Pad64)") (class "Default")
      (node (ref "IC6") (pin "64") (pinfunction "AN18/ERXERR/PMD4/RE4_64") (pintype "bidirectional"))
    )
    (net (code "194") (name "unconnected-(IC6-AN45{slash}C1INA{slash}RPB5{slash}RB5-Pad11)") (class "Default")
      (node (ref "IC6") (pin "11") (pinfunction "AN45/C1INA/RPB5/RB5_11") (pintype "bidirectional"))
    )
    (net (code "195") (name "unconnected-(IC6-AN48{slash}RPB8{slash}PMA10{slash}RB8-Pad21)") (class "Default")
      (node (ref "IC6") (pin "21") (pinfunction "AN48/RPB8/PMA10/RB8_21") (pintype "bidirectional"))
    )
    (net (code "196") (name "unconnected-(IC6-D+-Pad37)") (class "Default")
      (node (ref "IC6") (pin "37") (pinfunction "D+_37") (pintype "passive"))
    )
    (net (code "197") (name "unconnected-(IC6-D--Pad36)") (class "Default")
      (node (ref "IC6") (pin "36") (pinfunction "D-_36") (pintype "passive"))
    )
    (net (code "198") (name "unconnected-(IC6-ECOL{slash}RPD10{slash}SCL1{slash}SCK4{slash}RD10-Pad44)") (class "Default")
      (node (ref "IC6") (pin "44") (pinfunction "ECOL/RPD10/SCL1/SCK4/RD10_44") (pintype "bidirectional"))
    )
    (net (code "199") (name "unconnected-(IC6-ERXD3{slash}AETXD1{slash}RPF0{slash}RF0-Pad56)") (class "Default")
      (node (ref "IC6") (pin "56") (pinfunction "ERXD3/AETXD1/RPF0/RF0_56") (pintype "bidirectional"))
    )
    (net (code "200") (name "unconnected-(IC6-ETXERR{slash}AETXEN{slash}RPD2{slash}SDA3{slash}RD2-Pad50)") (class "Default")
      (node (ref "IC6") (pin "50") (pinfunction "ETXERR/AETXEN/RPD2/SDA3/RD2_50") (pintype "bidirectional"))
    )
    (net (code "201") (name "unconnected-(IC6-OSCO{slash}CLKO{slash}RC15-Pad32)") (class "Default")
      (node (ref "IC6") (pin "32") (pinfunction "OSCO/CLKO/RC15_32") (pintype "bidirectional"))
    )
    (net (code "202") (name "unconnected-(IC6-PGED2{slash}AN47{slash}RPB7{slash}RB7-Pad18)") (class "Default")
      (node (ref "IC6") (pin "18") (pinfunction "PGED2/AN47/RPB7/RB7_18") (pintype "bidirectional"))
    )
    (net (code "203") (name "unconnected-(IC6-RPF4{slash}SDA5{slash}PMA9{slash}RF4-Pad41)") (class "Default")
      (node (ref "IC6") (pin "41") (pinfunction "RPF4/SDA5/PMA9/RF4_41") (pintype "bidirectional"))
    )
    (net (code "204") (name "unconnected-(IC6-RPF5{slash}SCL5{slash}PMA8{slash}RF5-Pad42)") (class "Default")
      (node (ref "IC6") (pin "42") (pinfunction "RPF5/SCL5/PMA8/RF5_42") (pintype "bidirectional"))
    )
    (net (code "205") (name "unconnected-(IC6-TCK{slash}AN7{slash}PMA11{slash}RB12-Pad27)") (class "Default")
      (node (ref "IC6") (pin "27") (pinfunction "TCK/AN7/PMA11/RB12_27") (pintype "bidirectional"))
    )
    (net (code "206") (name "unconnected-(IC6-TDO{slash}AN6{slash}PMA12{slash}RB11-Pad24)") (class "Default")
      (node (ref "IC6") (pin "24") (pinfunction "TDO/AN6/PMA12/RB11_24") (pintype "bidirectional"))
    )
    (net (code "207") (name "unconnected-(IC6-TMS{slash}CVREFOUT{slash}AN5{slash}RPB10{slash}PMA13{slash}RB10-Pad23)") (class "Default")
      (node (ref "IC6") (pin "23") (pinfunction "TMS/CVREFOUT/AN5/RPB10/PMA13/RB10_23") (pintype "bidirectional"))
    )
    (net (code "208") (name "unconnected-(IC6-TRCLK{slash}SQICLK{slash}ERXD2{slash}AETXD0{slash}RPF1{slash}RF1-Pad57)") (class "Default")
      (node (ref "IC6") (pin "57") (pinfunction "TRCLK/SQICLK/ERXD2/AETXD0/RPF1/RF1_57") (pintype "bidirectional"))
    )
    (net (code "209") (name "unconnected-(IC6-TRD0{slash}SQID0{slash}ERXD1{slash}PMD0{slash}RE0-Pad58)") (class "Default")
      (node (ref "IC6") (pin "58") (pinfunction "TRD0/SQID0/ERXD1/PMD0/RE0_58") (pintype "bidirectional"))
    )
    (net (code "210") (name "unconnected-(IC6-TRD1{slash}SQID1{slash}ERXD0{slash}PMD1{slash}RE1-Pad61)") (class "Default")
      (node (ref "IC6") (pin "61") (pinfunction "TRD1/SQID1/ERXD0/PMD1/RE1_61") (pintype "bidirectional"))
    )
    (net (code "211") (name "unconnected-(IC6-TRD2{slash}SQID2{slash}ERXDV{slash}ECRSDV{slash}AECRSDV{slash}PMD2{slash}RE2-Pad62)") (class "Default")
      (node (ref "IC6") (pin "62") (pinfunction "TRD2/SQID2/ERXDV/ECRSDV/AECRSDV/PMD2/RE2_62") (pintype "bidirectional"))
    )
    (net (code "212") (name "unconnected-(IC6-TRD3{slash}SQID3{slash}ERXCLK{slash}EREFCLK{slash}RPE3{slash}PMD3{slash}RE3-Pad63)") (class "Default")
      (node (ref "IC6") (pin "63") (pinfunction "TRD3/SQID3/ERXCLK/EREFCLK/RPE3/PMD3/RE3_63") (pintype "bidirectional"))
    )
    (net (code "213") (name "unconnected-(IC8-~{THREE-STATE}-Pad3)") (class "Default")
      (node (ref "IC8") (pin "3") (pinfunction "~{THREE-STATE}_3") (pintype "bidirectional"))
    )
    (net (code "214") (name "unconnected-(IC11-CLKOUT-Pad27)") (class "Default")
      (node (ref "IC11") (pin "27") (pinfunction "CLKOUT_27") (pintype "output"))
    )
    (net (code "215") (name "unconnected-(IC11-EP-Pad29)") (class "Default")
      (node (ref "IC11") (pin "29") (pinfunction "EP_29") (pintype "passive"))
    )
    (net (code "216") (name "unconnected-(IC11-NC-Pad1)") (class "Default")
      (node (ref "IC11") (pin "1") (pinfunction "NC_1") (pintype "no_connect"))
    )
    (net (code "217") (name "unconnected-(IC11-~{INT}-Pad28)") (class "Default")
      (node (ref "IC11") (pin "28") (pinfunction "~{INT}_28") (pintype "output"))
    )
    (net (code "218") (name "unconnected-(IC12-NC-Pad13)") (class "Default")
      (node (ref "IC12") (pin "13") (pinfunction "NC_13") (pintype "bidirectional"))
    )
    (net (code "219") (name "unconnected-(IC12-RB2{slash}AN8{slash}INT2{slash}VMO-Pad11)") (class "Default")
      (node (ref "IC12") (pin "11") (pinfunction "RB2/AN8/INT2/VMO_11") (pintype "bidirectional"))
    )
    (net (code "220") (name "unconnected-(IC12-RB3{slash}AN9{slash}CCP2{slash}VPO-Pad12)") (class "Default")
      (node (ref "IC12") (pin "12") (pinfunction "RB3/AN9/CCP2/VPO_12") (pintype "bidirectional"))
    )
    (net (code "221") (name "unconnected-(IC12-RB5{slash}KBI1{slash}PGM-Pad15)") (class "Default")
      (node (ref "IC12") (pin "15") (pinfunction "RB5/KBI1/PGM_15") (pintype "bidirectional"))
    )
    (net (code "222") (name "unconnected-(IC12-RE2{slash}AN7{slash}OESPP-Pad27)") (class "Default")
      (node (ref "IC12") (pin "27") (pinfunction "RE2/AN7/OESPP_27") (pintype "bidirectional"))
    )
    (net (code "223") (name "unconnected-(IC12-VUSB-Pad37)") (class "Default")
      (node (ref "IC12") (pin "37") (pinfunction "VUSB_37") (pintype "bidirectional"))
    )
    (net (code "224") (name "unconnected-(JP1-Pad4)") (class "Default")
      (node (ref "JP1") (pin "4") (pinfunction "4_4") (pintype "passive"))
    )
    (net (code "225") (name "unconnected-(JP3-Pad4)") (class "Default")
      (node (ref "JP3") (pin "4") (pinfunction "4_4") (pintype "passive"))
    )
    (net (code "226") (name "unconnected-(JP4-Pad4)") (class "Default")
      (node (ref "JP4") (pin "4") (pinfunction "4_4") (pintype "passive"))
    )
    (net (code "227") (name "unconnected-(K2B-O-Pad7)") (class "Default")
      (node (ref "K2") (pin "7") (pinfunction "O_7") (pintype "passive"))
    )
    (net (code "228") (name "unconnected-(S1-O-Pad3)") (class "Default")
      (node (ref "S1") (pin "3") (pinfunction "O_3") (pintype "passive"))
    )
    (net (code "229") (name "unconnected-(X1-Pad4)") (class "Default")
      (node (ref "X1") (pin "4") (pinfunction "4_4") (pintype "input"))
    )
    (net (code "230") (name "unconnected-(X4-NC{slash}4-Pad4)") (class "Default")
      (node (ref "X4") (pin "4") (pinfunction "NC/4_4") (pintype "input"))
    )
    (net (code "231") (name "unconnected-(X4-NC{slash}5-Pad5)") (class "Default")
      (node (ref "X4") (pin "5") (pinfunction "NC/5_5") (pintype "input"))
    )
  )
)
